# untitled.net
KiCad netlist of a schematic drawn in EAGLE
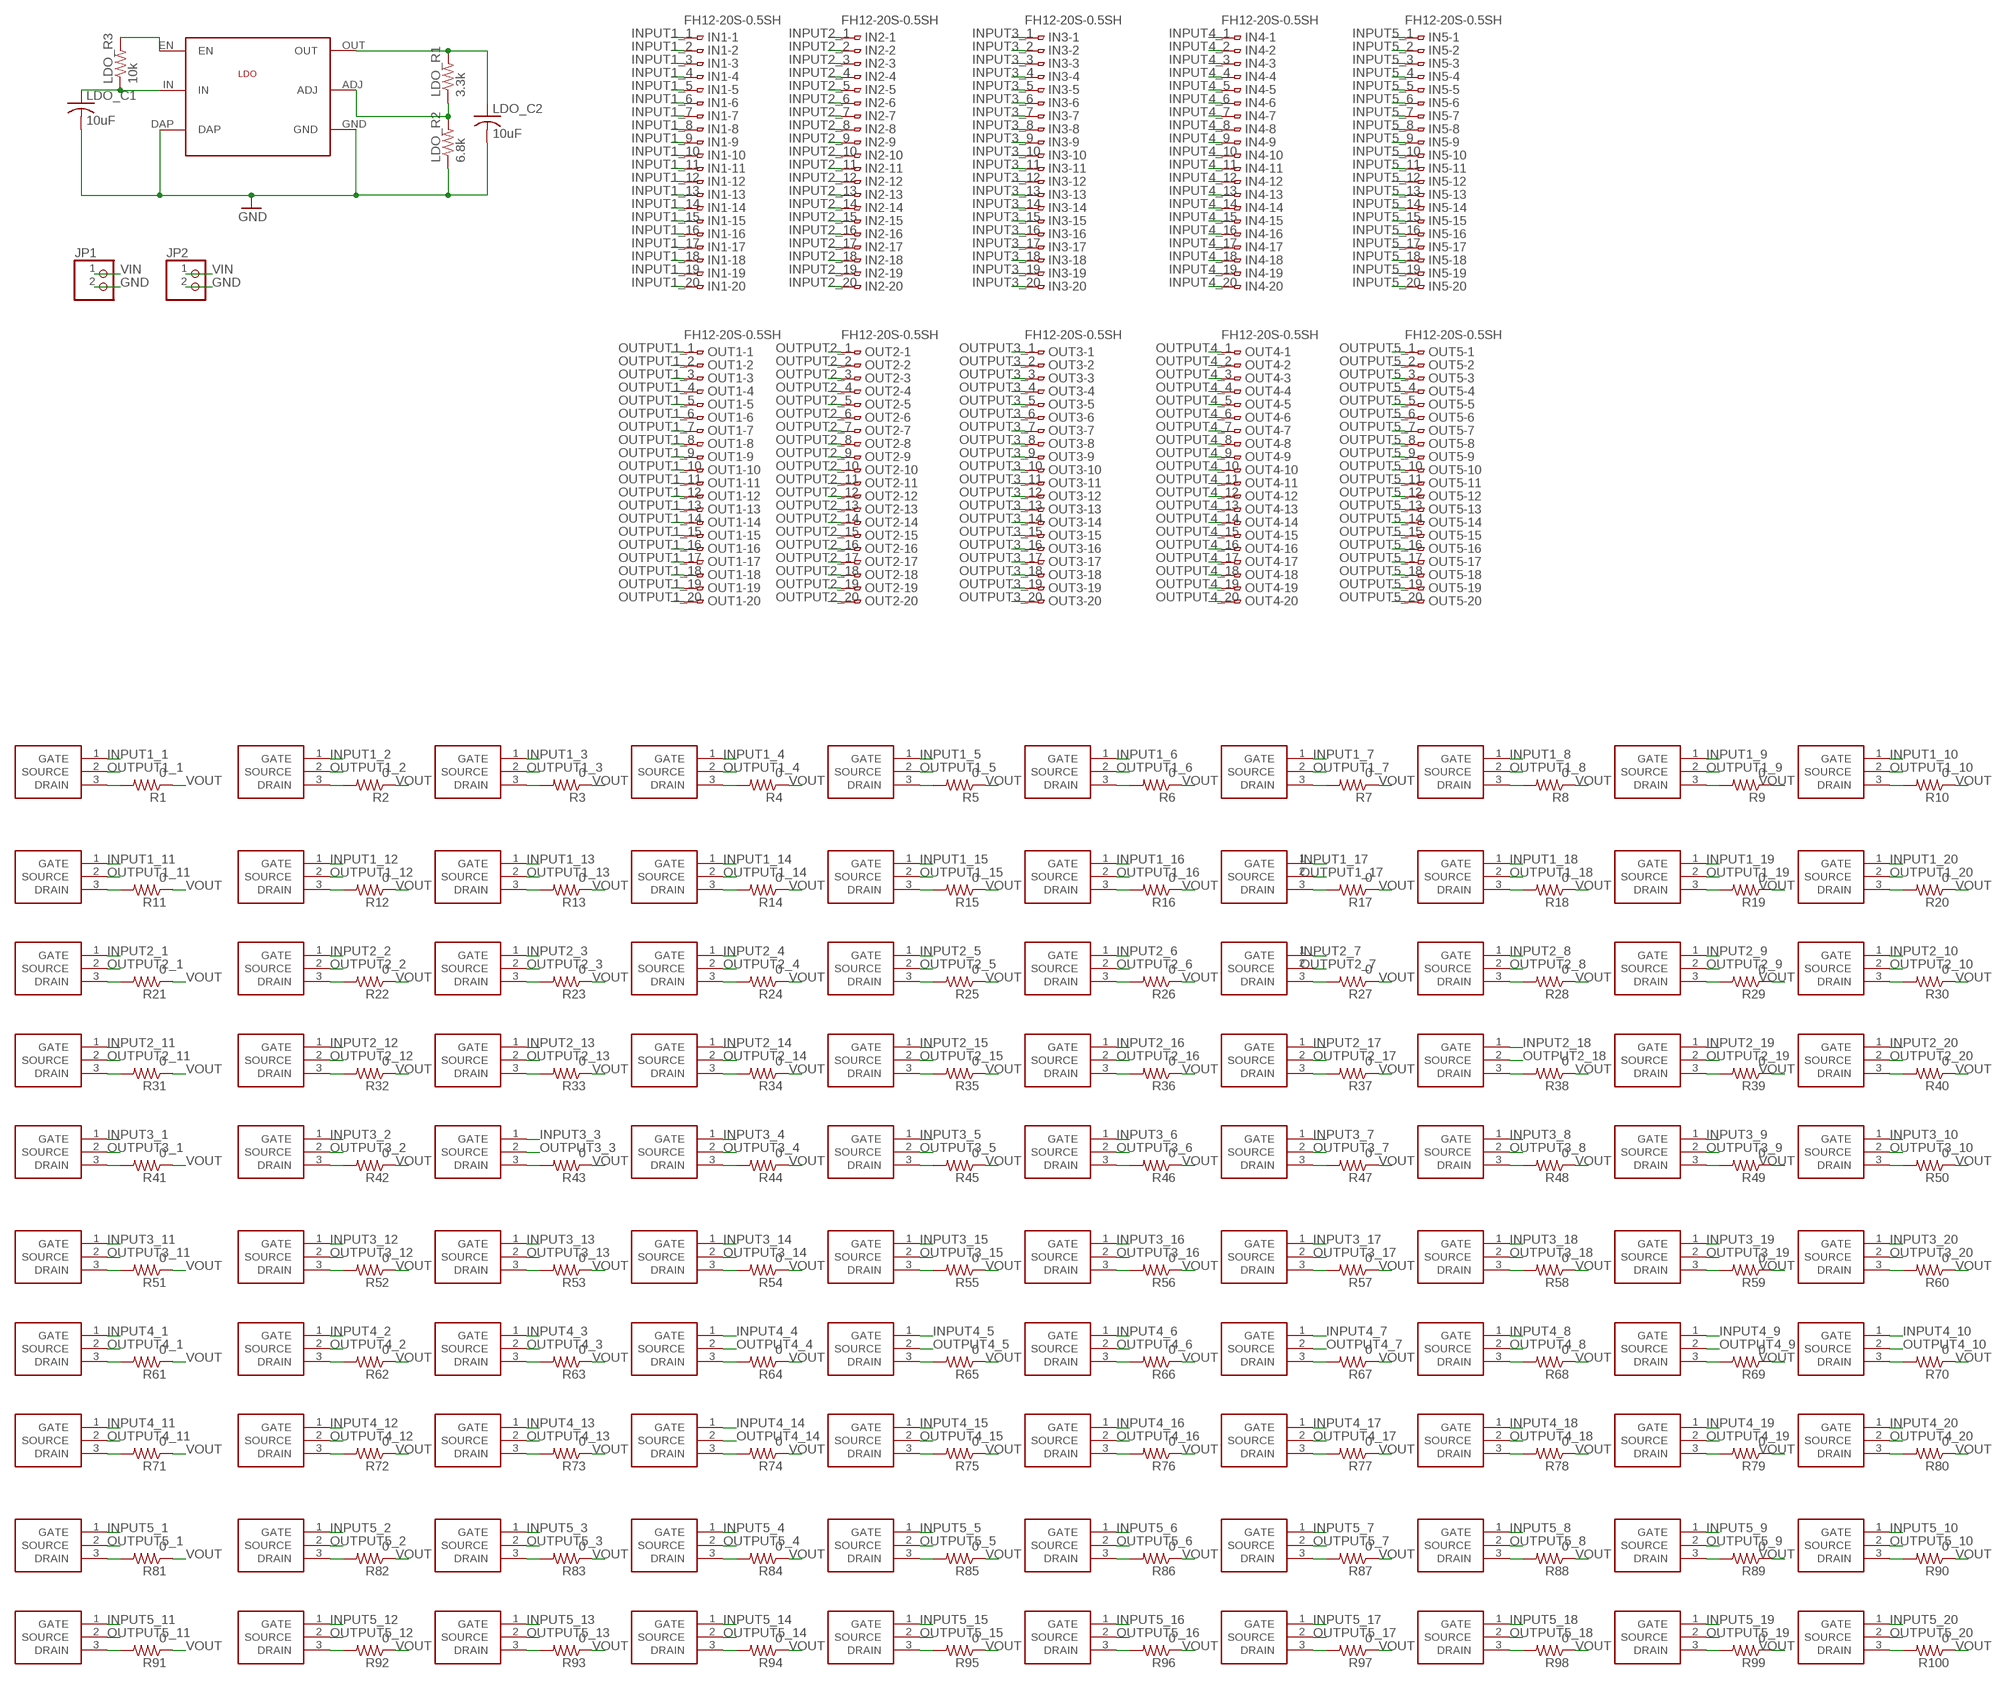
[diagram p0: schematic, sheet 1]

(export (version "E")
  (design (tool "Eeschema 10.0.6"))
  (components
    (comp (ref "IN1")
      (value "FH12-20S-0.5SH")
      (footprint "eagle-import:FH12-20S-0.5SH")
      (fields (field (name "MPN") "FH12-20S-0.5SH(55)"))
      (libsource (lib "eagle-import") (part "FH12-20S-0.5SH"))
    )
    (comp (ref "IN2")
      (value "FH12-20S-0.5SH")
      (footprint "eagle-import:FH12-20S-0.5SH")
      (fields (field (name "MPN") "FH12-20S-0.5SH(55)"))
      (libsource (lib "eagle-import") (part "FH12-20S-0.5SH"))
    )
    (comp (ref "IN3")
      (value "FH12-20S-0.5SH")
      (footprint "eagle-import:FH12-20S-0.5SH")
      (fields (field (name "MPN") "FH12-20S-0.5SH(55)"))
      (libsource (lib "eagle-import") (part "FH12-20S-0.5SH"))
    )
    (comp (ref "IN4")
      (value "FH12-20S-0.5SH")
      (footprint "eagle-import:FH12-20S-0.5SH")
      (fields (field (name "MPN") "FH12-20S-0.5SH(55)"))
      (libsource (lib "eagle-import") (part "FH12-20S-0.5SH"))
    )
    (comp (ref "IN5")
      (value "FH12-20S-0.5SH")
      (footprint "eagle-import:FH12-20S-0.5SH")
      (fields (field (name "MPN") "FH12-20S-0.5SH(55)"))
      (libsource (lib "eagle-import") (part "FH12-20S-0.5SH"))
    )
    (comp (ref "JP1")
      (value "PINHD-1X2")
      (footprint "eagle-import:1X02")
      (libsource (lib "eagle-import") (part "PINHD-1X2"))
    )
    (comp (ref "JP2")
      (value "PINHD-1X2")
      (footprint "eagle-import:1X02")
      (libsource (lib "eagle-import") (part "PINHD-1X2"))
    )
    (comp (ref "LDO")
      (value "LP38501TS_ADJ")
      (footprint "eagle-import:LP38501TS_ADJ")
      (libsource (lib "eagle-import") (part "LP38501TS_ADJ"))
    )
    (comp (ref "LDO_C1")
      (value "10uF")
      (footprint "eagle-import:C0805")
      (libsource (lib "eagle-import") (part "C-USC0805"))
    )
    (comp (ref "LDO_C2")
      (value "10uF")
      (footprint "eagle-import:C0805")
      (libsource (lib "eagle-import") (part "C-USC0805"))
    )
    (comp (ref "LDO_R1")
      (value "3.3k")
      (footprint "eagle-import:R0805")
      (libsource (lib "eagle-import") (part "R-US_R0805"))
    )
    (comp (ref "LDO_R2")
      (value "6.8k")
      (footprint "eagle-import:R0805")
      (libsource (lib "eagle-import") (part "R-US_R0805"))
    )
    (comp (ref "LDO_R3")
      (value "10k")
      (footprint "eagle-import:R0805")
      (libsource (lib "eagle-import") (part "R-US_R0805"))
    )
    (comp (ref "MOS1")
      (value "NX6008NBKNX6008NBK")
      (footprint "eagle-import:SOT95P240X110-3N")
      (libsource (lib "eagle-import") (part "NX6008NBKNX6008NBK"))
    )
    (comp (ref "MOS2")
      (value "NX6008NBKNX6008NBK")
      (footprint "eagle-import:SOT95P240X110-3N")
      (libsource (lib "eagle-import") (part "NX6008NBKNX6008NBK"))
    )
    (comp (ref "MOS3")
      (value "NX6008NBKNX6008NBK")
      (footprint "eagle-import:SOT95P240X110-3N")
      (libsource (lib "eagle-import") (part "NX6008NBKNX6008NBK"))
    )
    (comp (ref "MOS4")
      (value "NX6008NBKNX6008NBK")
      (footprint "eagle-import:SOT95P240X110-3N")
      (libsource (lib "eagle-import") (part "NX6008NBKNX6008NBK"))
    )
    (comp (ref "MOS5")
      (value "NX6008NBKNX6008NBK")
      (footprint "eagle-import:SOT95P240X110-3N")
      (libsource (lib "eagle-import") (part "NX6008NBKNX6008NBK"))
    )
    (comp (ref "MOS6")
      (value "NX6008NBKNX6008NBK")
      (footprint "eagle-import:SOT95P240X110-3N")
      (libsource (lib "eagle-import") (part "NX6008NBKNX6008NBK"))
    )
    (comp (ref "MOS7")
      (value "NX6008NBKNX6008NBK")
      (footprint "eagle-import:SOT95P240X110-3N")
      (libsource (lib "eagle-import") (part "NX6008NBKNX6008NBK"))
    )
    (comp (ref "MOS8")
      (value "NX6008NBKNX6008NBK")
      (footprint "eagle-import:SOT95P240X110-3N")
      (libsource (lib "eagle-import") (part "NX6008NBKNX6008NBK"))
    )
    (comp (ref "MOS9")
      (value "NX6008NBKNX6008NBK")
      (footprint "eagle-import:SOT95P240X110-3N")
      (libsource (lib "eagle-import") (part "NX6008NBKNX6008NBK"))
    )
    (comp (ref "MOS10")
      (value "NX6008NBKNX6008NBK")
      (footprint "eagle-import:SOT95P240X110-3N")
      (libsource (lib "eagle-import") (part "NX6008NBKNX6008NBK"))
    )
    (comp (ref "MOS11")
      (value "NX6008NBKNX6008NBK")
      (footprint "eagle-import:SOT95P240X110-3N")
      (libsource (lib "eagle-import") (part "NX6008NBKNX6008NBK"))
    )
    (comp (ref "MOS12")
      (value "NX6008NBKNX6008NBK")
      (footprint "eagle-import:SOT95P240X110-3N")
      (libsource (lib "eagle-import") (part "NX6008NBKNX6008NBK"))
    )
    (comp (ref "MOS13")
      (value "NX6008NBKNX6008NBK")
      (footprint "eagle-import:SOT95P240X110-3N")
      (libsource (lib "eagle-import") (part "NX6008NBKNX6008NBK"))
    )
    (comp (ref "MOS14")
      (value "NX6008NBKNX6008NBK")
      (footprint "eagle-import:SOT95P240X110-3N")
      (libsource (lib "eagle-import") (part "NX6008NBKNX6008NBK"))
    )
    (comp (ref "MOS15")
      (value "NX6008NBKNX6008NBK")
      (footprint "eagle-import:SOT95P240X110-3N")
      (libsource (lib "eagle-import") (part "NX6008NBKNX6008NBK"))
    )
    (comp (ref "MOS16")
      (value "NX6008NBKNX6008NBK")
      (footprint "eagle-import:SOT95P240X110-3N")
      (libsource (lib "eagle-import") (part "NX6008NBKNX6008NBK"))
    )
    (comp (ref "MOS17")
      (value "NX6008NBKNX6008NBK")
      (footprint "eagle-import:SOT95P240X110-3N")
      (libsource (lib "eagle-import") (part "NX6008NBKNX6008NBK"))
    )
    (comp (ref "MOS18")
      (value "NX6008NBKNX6008NBK")
      (footprint "eagle-import:SOT95P240X110-3N")
      (libsource (lib "eagle-import") (part "NX6008NBKNX6008NBK"))
    )
    (comp (ref "MOS19")
      (value "NX6008NBKNX6008NBK")
      (footprint "eagle-import:SOT95P240X110-3N")
      (libsource (lib "eagle-import") (part "NX6008NBKNX6008NBK"))
    )
    (comp (ref "MOS20")
      (value "NX6008NBKNX6008NBK")
      (footprint "eagle-import:SOT95P240X110-3N")
      (libsource (lib "eagle-import") (part "NX6008NBKNX6008NBK"))
    )
    (comp (ref "MOS21")
      (value "NX6008NBKNX6008NBK")
      (footprint "eagle-import:SOT95P240X110-3N")
      (libsource (lib "eagle-import") (part "NX6008NBKNX6008NBK"))
    )
    (comp (ref "MOS22")
      (value "NX6008NBKNX6008NBK")
      (footprint "eagle-import:SOT95P240X110-3N")
      (libsource (lib "eagle-import") (part "NX6008NBKNX6008NBK"))
    )
    (comp (ref "MOS23")
      (value "NX6008NBKNX6008NBK")
      (footprint "eagle-import:SOT95P240X110-3N")
      (libsource (lib "eagle-import") (part "NX6008NBKNX6008NBK"))
    )
    (comp (ref "MOS24")
      (value "NX6008NBKNX6008NBK")
      (footprint "eagle-import:SOT95P240X110-3N")
      (libsource (lib "eagle-import") (part "NX6008NBKNX6008NBK"))
    )
    (comp (ref "MOS25")
      (value "NX6008NBKNX6008NBK")
      (footprint "eagle-import:SOT95P240X110-3N")
      (libsource (lib "eagle-import") (part "NX6008NBKNX6008NBK"))
    )
    (comp (ref "MOS26")
      (value "NX6008NBKNX6008NBK")
      (footprint "eagle-import:SOT95P240X110-3N")
      (libsource (lib "eagle-import") (part "NX6008NBKNX6008NBK"))
    )
    (comp (ref "MOS27")
      (value "NX6008NBKNX6008NBK")
      (footprint "eagle-import:SOT95P240X110-3N")
      (libsource (lib "eagle-import") (part "NX6008NBKNX6008NBK"))
    )
    (comp (ref "MOS28")
      (value "NX6008NBKNX6008NBK")
      (footprint "eagle-import:SOT95P240X110-3N")
      (libsource (lib "eagle-import") (part "NX6008NBKNX6008NBK"))
    )
    (comp (ref "MOS29")
      (value "NX6008NBKNX6008NBK")
      (footprint "eagle-import:SOT95P240X110-3N")
      (libsource (lib "eagle-import") (part "NX6008NBKNX6008NBK"))
    )
    (comp (ref "MOS30")
      (value "NX6008NBKNX6008NBK")
      (footprint "eagle-import:SOT95P240X110-3N")
      (libsource (lib "eagle-import") (part "NX6008NBKNX6008NBK"))
    )
    (comp (ref "MOS31")
      (value "NX6008NBKNX6008NBK")
      (footprint "eagle-import:SOT95P240X110-3N")
      (libsource (lib "eagle-import") (part "NX6008NBKNX6008NBK"))
    )
    (comp (ref "MOS32")
      (value "NX6008NBKNX6008NBK")
      (footprint "eagle-import:SOT95P240X110-3N")
      (libsource (lib "eagle-import") (part "NX6008NBKNX6008NBK"))
    )
    (comp (ref "MOS33")
      (value "NX6008NBKNX6008NBK")
      (footprint "eagle-import:SOT95P240X110-3N")
      (libsource (lib "eagle-import") (part "NX6008NBKNX6008NBK"))
    )
    (comp (ref "MOS34")
      (value "NX6008NBKNX6008NBK")
      (footprint "eagle-import:SOT95P240X110-3N")
      (libsource (lib "eagle-import") (part "NX6008NBKNX6008NBK"))
    )
    (comp (ref "MOS35")
      (value "NX6008NBKNX6008NBK")
      (footprint "eagle-import:SOT95P240X110-3N")
      (libsource (lib "eagle-import") (part "NX6008NBKNX6008NBK"))
    )
    (comp (ref "MOS36")
      (value "NX6008NBKNX6008NBK")
      (footprint "eagle-import:SOT95P240X110-3N")
      (libsource (lib "eagle-import") (part "NX6008NBKNX6008NBK"))
    )
    (comp (ref "MOS37")
      (value "NX6008NBKNX6008NBK")
      (footprint "eagle-import:SOT95P240X110-3N")
      (libsource (lib "eagle-import") (part "NX6008NBKNX6008NBK"))
    )
    (comp (ref "MOS38")
      (value "NX6008NBKNX6008NBK")
      (footprint "eagle-import:SOT95P240X110-3N")
      (libsource (lib "eagle-import") (part "NX6008NBKNX6008NBK"))
    )
    (comp (ref "MOS39")
      (value "NX6008NBKNX6008NBK")
      (footprint "eagle-import:SOT95P240X110-3N")
      (libsource (lib "eagle-import") (part "NX6008NBKNX6008NBK"))
    )
    (comp (ref "MOS40")
      (value "NX6008NBKNX6008NBK")
      (footprint "eagle-import:SOT95P240X110-3N")
      (libsource (lib "eagle-import") (part "NX6008NBKNX6008NBK"))
    )
    (comp (ref "MOS41")
      (value "NX6008NBKNX6008NBK")
      (footprint "eagle-import:SOT95P240X110-3N")
      (libsource (lib "eagle-import") (part "NX6008NBKNX6008NBK"))
    )
    (comp (ref "MOS42")
      (value "NX6008NBKNX6008NBK")
      (footprint "eagle-import:SOT95P240X110-3N")
      (libsource (lib "eagle-import") (part "NX6008NBKNX6008NBK"))
    )
    (comp (ref "MOS43")
      (value "NX6008NBKNX6008NBK")
      (footprint "eagle-import:SOT95P240X110-3N")
      (libsource (lib "eagle-import") (part "NX6008NBKNX6008NBK"))
    )
    (comp (ref "MOS44")
      (value "NX6008NBKNX6008NBK")
      (footprint "eagle-import:SOT95P240X110-3N")
      (libsource (lib "eagle-import") (part "NX6008NBKNX6008NBK"))
    )
    (comp (ref "MOS45")
      (value "NX6008NBKNX6008NBK")
      (footprint "eagle-import:SOT95P240X110-3N")
      (libsource (lib "eagle-import") (part "NX6008NBKNX6008NBK"))
    )
    (comp (ref "MOS46")
      (value "NX6008NBKNX6008NBK")
      (footprint "eagle-import:SOT95P240X110-3N")
      (libsource (lib "eagle-import") (part "NX6008NBKNX6008NBK"))
    )
    (comp (ref "MOS47")
      (value "NX6008NBKNX6008NBK")
      (footprint "eagle-import:SOT95P240X110-3N")
      (libsource (lib "eagle-import") (part "NX6008NBKNX6008NBK"))
    )
    (comp (ref "MOS48")
      (value "NX6008NBKNX6008NBK")
      (footprint "eagle-import:SOT95P240X110-3N")
      (libsource (lib "eagle-import") (part "NX6008NBKNX6008NBK"))
    )
    (comp (ref "MOS49")
      (value "NX6008NBKNX6008NBK")
      (footprint "eagle-import:SOT95P240X110-3N")
      (libsource (lib "eagle-import") (part "NX6008NBKNX6008NBK"))
    )
    (comp (ref "MOS50")
      (value "NX6008NBKNX6008NBK")
      (footprint "eagle-import:SOT95P240X110-3N")
      (libsource (lib "eagle-import") (part "NX6008NBKNX6008NBK"))
    )
    (comp (ref "MOS51")
      (value "NX6008NBKNX6008NBK")
      (footprint "eagle-import:SOT95P240X110-3N")
      (libsource (lib "eagle-import") (part "NX6008NBKNX6008NBK"))
    )
    (comp (ref "MOS52")
      (value "NX6008NBKNX6008NBK")
      (footprint "eagle-import:SOT95P240X110-3N")
      (libsource (lib "eagle-import") (part "NX6008NBKNX6008NBK"))
    )
    (comp (ref "MOS53")
      (value "NX6008NBKNX6008NBK")
      (footprint "eagle-import:SOT95P240X110-3N")
      (libsource (lib "eagle-import") (part "NX6008NBKNX6008NBK"))
    )
    (comp (ref "MOS54")
      (value "NX6008NBKNX6008NBK")
      (footprint "eagle-import:SOT95P240X110-3N")
      (libsource (lib "eagle-import") (part "NX6008NBKNX6008NBK"))
    )
    (comp (ref "MOS55")
      (value "NX6008NBKNX6008NBK")
      (footprint "eagle-import:SOT95P240X110-3N")
      (libsource (lib "eagle-import") (part "NX6008NBKNX6008NBK"))
    )
    (comp (ref "MOS56")
      (value "NX6008NBKNX6008NBK")
      (footprint "eagle-import:SOT95P240X110-3N")
      (libsource (lib "eagle-import") (part "NX6008NBKNX6008NBK"))
    )
    (comp (ref "MOS57")
      (value "NX6008NBKNX6008NBK")
      (footprint "eagle-import:SOT95P240X110-3N")
      (libsource (lib "eagle-import") (part "NX6008NBKNX6008NBK"))
    )
    (comp (ref "MOS58")
      (value "NX6008NBKNX6008NBK")
      (footprint "eagle-import:SOT95P240X110-3N")
      (libsource (lib "eagle-import") (part "NX6008NBKNX6008NBK"))
    )
    (comp (ref "MOS59")
      (value "NX6008NBKNX6008NBK")
      (footprint "eagle-import:SOT95P240X110-3N")
      (libsource (lib "eagle-import") (part "NX6008NBKNX6008NBK"))
    )
    (comp (ref "MOS60")
      (value "NX6008NBKNX6008NBK")
      (footprint "eagle-import:SOT95P240X110-3N")
      (libsource (lib "eagle-import") (part "NX6008NBKNX6008NBK"))
    )
    (comp (ref "MOS61")
      (value "NX6008NBKNX6008NBK")
      (footprint "eagle-import:SOT95P240X110-3N")
      (libsource (lib "eagle-import") (part "NX6008NBKNX6008NBK"))
    )
    (comp (ref "MOS62")
      (value "NX6008NBKNX6008NBK")
      (footprint "eagle-import:SOT95P240X110-3N")
      (libsource (lib "eagle-import") (part "NX6008NBKNX6008NBK"))
    )
    (comp (ref "MOS63")
      (value "NX6008NBKNX6008NBK")
      (footprint "eagle-import:SOT95P240X110-3N")
      (libsource (lib "eagle-import") (part "NX6008NBKNX6008NBK"))
    )
    (comp (ref "MOS64")
      (value "NX6008NBKNX6008NBK")
      (footprint "eagle-import:SOT95P240X110-3N")
      (libsource (lib "eagle-import") (part "NX6008NBKNX6008NBK"))
    )
    (comp (ref "MOS65")
      (value "NX6008NBKNX6008NBK")
      (footprint "eagle-import:SOT95P240X110-3N")
      (libsource (lib "eagle-import") (part "NX6008NBKNX6008NBK"))
    )
    (comp (ref "MOS66")
      (value "NX6008NBKNX6008NBK")
      (footprint "eagle-import:SOT95P240X110-3N")
      (libsource (lib "eagle-import") (part "NX6008NBKNX6008NBK"))
    )
    (comp (ref "MOS67")
      (value "NX6008NBKNX6008NBK")
      (footprint "eagle-import:SOT95P240X110-3N")
      (libsource (lib "eagle-import") (part "NX6008NBKNX6008NBK"))
    )
    (comp (ref "MOS68")
      (value "NX6008NBKNX6008NBK")
      (footprint "eagle-import:SOT95P240X110-3N")
      (libsource (lib "eagle-import") (part "NX6008NBKNX6008NBK"))
    )
    (comp (ref "MOS69")
      (value "NX6008NBKNX6008NBK")
      (footprint "eagle-import:SOT95P240X110-3N")
      (libsource (lib "eagle-import") (part "NX6008NBKNX6008NBK"))
    )
    (comp (ref "MOS70")
      (value "NX6008NBKNX6008NBK")
      (footprint "eagle-import:SOT95P240X110-3N")
      (libsource (lib "eagle-import") (part "NX6008NBKNX6008NBK"))
    )
    (comp (ref "MOS71")
      (value "NX6008NBKNX6008NBK")
      (footprint "eagle-import:SOT95P240X110-3N")
      (libsource (lib "eagle-import") (part "NX6008NBKNX6008NBK"))
    )
    (comp (ref "MOS72")
      (value "NX6008NBKNX6008NBK")
      (footprint "eagle-import:SOT95P240X110-3N")
      (libsource (lib "eagle-import") (part "NX6008NBKNX6008NBK"))
    )
    (comp (ref "MOS73")
      (value "NX6008NBKNX6008NBK")
      (footprint "eagle-import:SOT95P240X110-3N")
      (libsource (lib "eagle-import") (part "NX6008NBKNX6008NBK"))
    )
    (comp (ref "MOS74")
      (value "NX6008NBKNX6008NBK")
      (footprint "eagle-import:SOT95P240X110-3N")
      (libsource (lib "eagle-import") (part "NX6008NBKNX6008NBK"))
    )
    (comp (ref "MOS75")
      (value "NX6008NBKNX6008NBK")
      (footprint "eagle-import:SOT95P240X110-3N")
      (libsource (lib "eagle-import") (part "NX6008NBKNX6008NBK"))
    )
    (comp (ref "MOS76")
      (value "NX6008NBKNX6008NBK")
      (footprint "eagle-import:SOT95P240X110-3N")
      (libsource (lib "eagle-import") (part "NX6008NBKNX6008NBK"))
    )
    (comp (ref "MOS77")
      (value "NX6008NBKNX6008NBK")
      (footprint "eagle-import:SOT95P240X110-3N")
      (libsource (lib "eagle-import") (part "NX6008NBKNX6008NBK"))
    )
    (comp (ref "MOS78")
      (value "NX6008NBKNX6008NBK")
      (footprint "eagle-import:SOT95P240X110-3N")
      (libsource (lib "eagle-import") (part "NX6008NBKNX6008NBK"))
    )
    (comp (ref "MOS79")
      (value "NX6008NBKNX6008NBK")
      (footprint "eagle-import:SOT95P240X110-3N")
      (libsource (lib "eagle-import") (part "NX6008NBKNX6008NBK"))
    )
    (comp (ref "MOS80")
      (value "NX6008NBKNX6008NBK")
      (footprint "eagle-import:SOT95P240X110-3N")
      (libsource (lib "eagle-import") (part "NX6008NBKNX6008NBK"))
    )
    (comp (ref "MOS81")
      (value "NX6008NBKNX6008NBK")
      (footprint "eagle-import:SOT95P240X110-3N")
      (libsource (lib "eagle-import") (part "NX6008NBKNX6008NBK"))
    )
    (comp (ref "MOS82")
      (value "NX6008NBKNX6008NBK")
      (footprint "eagle-import:SOT95P240X110-3N")
      (libsource (lib "eagle-import") (part "NX6008NBKNX6008NBK"))
    )
    (comp (ref "MOS83")
      (value "NX6008NBKNX6008NBK")
      (footprint "eagle-import:SOT95P240X110-3N")
      (libsource (lib "eagle-import") (part "NX6008NBKNX6008NBK"))
    )
    (comp (ref "MOS84")
      (value "NX6008NBKNX6008NBK")
      (footprint "eagle-import:SOT95P240X110-3N")
      (libsource (lib "eagle-import") (part "NX6008NBKNX6008NBK"))
    )
    (comp (ref "MOS85")
      (value "NX6008NBKNX6008NBK")
      (footprint "eagle-import:SOT95P240X110-3N")
      (libsource (lib "eagle-import") (part "NX6008NBKNX6008NBK"))
    )
    (comp (ref "MOS86")
      (value "NX6008NBKNX6008NBK")
      (footprint "eagle-import:SOT95P240X110-3N")
      (libsource (lib "eagle-import") (part "NX6008NBKNX6008NBK"))
    )
    (comp (ref "MOS87")
      (value "NX6008NBKNX6008NBK")
      (footprint "eagle-import:SOT95P240X110-3N")
      (libsource (lib "eagle-import") (part "NX6008NBKNX6008NBK"))
    )
    (comp (ref "MOS88")
      (value "NX6008NBKNX6008NBK")
      (footprint "eagle-import:SOT95P240X110-3N")
      (libsource (lib "eagle-import") (part "NX6008NBKNX6008NBK"))
    )
    (comp (ref "MOS89")
      (value "NX6008NBKNX6008NBK")
      (footprint "eagle-import:SOT95P240X110-3N")
      (libsource (lib "eagle-import") (part "NX6008NBKNX6008NBK"))
    )
    (comp (ref "MOS90")
      (value "NX6008NBKNX6008NBK")
      (footprint "eagle-import:SOT95P240X110-3N")
      (libsource (lib "eagle-import") (part "NX6008NBKNX6008NBK"))
    )
    (comp (ref "MOS91")
      (value "NX6008NBKNX6008NBK")
      (footprint "eagle-import:SOT95P240X110-3N")
      (libsource (lib "eagle-import") (part "NX6008NBKNX6008NBK"))
    )
    (comp (ref "MOS92")
      (value "NX6008NBKNX6008NBK")
      (footprint "eagle-import:SOT95P240X110-3N")
      (libsource (lib "eagle-import") (part "NX6008NBKNX6008NBK"))
    )
    (comp (ref "MOS93")
      (value "NX6008NBKNX6008NBK")
      (footprint "eagle-import:SOT95P240X110-3N")
      (libsource (lib "eagle-import") (part "NX6008NBKNX6008NBK"))
    )
    (comp (ref "MOS94")
      (value "NX6008NBKNX6008NBK")
      (footprint "eagle-import:SOT95P240X110-3N")
      (libsource (lib "eagle-import") (part "NX6008NBKNX6008NBK"))
    )
    (comp (ref "MOS95")
      (value "NX6008NBKNX6008NBK")
      (footprint "eagle-import:SOT95P240X110-3N")
      (libsource (lib "eagle-import") (part "NX6008NBKNX6008NBK"))
    )
    (comp (ref "MOS96")
      (value "NX6008NBKNX6008NBK")
      (footprint "eagle-import:SOT95P240X110-3N")
      (libsource (lib "eagle-import") (part "NX6008NBKNX6008NBK"))
    )
    (comp (ref "MOS97")
      (value "NX6008NBKNX6008NBK")
      (footprint "eagle-import:SOT95P240X110-3N")
      (libsource (lib "eagle-import") (part "NX6008NBKNX6008NBK"))
    )
    (comp (ref "MOS98")
      (value "NX6008NBKNX6008NBK")
      (footprint "eagle-import:SOT95P240X110-3N")
      (libsource (lib "eagle-import") (part "NX6008NBKNX6008NBK"))
    )
    (comp (ref "MOS99")
      (value "NX6008NBKNX6008NBK")
      (footprint "eagle-import:SOT95P240X110-3N")
      (libsource (lib "eagle-import") (part "NX6008NBKNX6008NBK"))
    )
    (comp (ref "MOS100")
      (value "NX6008NBKNX6008NBK")
      (footprint "eagle-import:SOT95P240X110-3N")
      (libsource (lib "eagle-import") (part "NX6008NBKNX6008NBK"))
    )
    (comp (ref "OUT1")
      (value "FH12-20S-0.5SH")
      (footprint "eagle-import:FH12-20S-0.5SH")
      (fields (field (name "MPN") "FH12-20S-0.5SH(55)"))
      (libsource (lib "eagle-import") (part "FH12-20S-0.5SH"))
    )
    (comp (ref "OUT2")
      (value "FH12-20S-0.5SH")
      (footprint "eagle-import:FH12-20S-0.5SH")
      (fields (field (name "MPN") "FH12-20S-0.5SH(55)"))
      (libsource (lib "eagle-import") (part "FH12-20S-0.5SH"))
    )
    (comp (ref "OUT3")
      (value "FH12-20S-0.5SH")
      (footprint "eagle-import:FH12-20S-0.5SH")
      (fields (field (name "MPN") "FH12-20S-0.5SH(55)"))
      (libsource (lib "eagle-import") (part "FH12-20S-0.5SH"))
    )
    (comp (ref "OUT4")
      (value "FH12-20S-0.5SH")
      (footprint "eagle-import:FH12-20S-0.5SH")
      (fields (field (name "MPN") "FH12-20S-0.5SH(55)"))
      (libsource (lib "eagle-import") (part "FH12-20S-0.5SH"))
    )
    (comp (ref "OUT5")
      (value "FH12-20S-0.5SH")
      (footprint "eagle-import:FH12-20S-0.5SH")
      (fields (field (name "MPN") "FH12-20S-0.5SH(55)"))
      (libsource (lib "eagle-import") (part "FH12-20S-0.5SH"))
    )
    (comp (ref "R1")
      (value "0")
      (footprint "eagle-import:R0805")
      (libsource (lib "eagle-import") (part "R-US_R0805"))
    )
    (comp (ref "R2")
      (value "0")
      (footprint "eagle-import:R0805")
      (libsource (lib "eagle-import") (part "R-US_R0805"))
    )
    (comp (ref "R3")
      (value "0")
      (footprint "eagle-import:R0805")
      (libsource (lib "eagle-import") (part "R-US_R0805"))
    )
    (comp (ref "R4")
      (value "0")
      (footprint "eagle-import:R0805")
      (libsource (lib "eagle-import") (part "R-US_R0805"))
    )
    (comp (ref "R5")
      (value "0")
      (footprint "eagle-import:R0805")
      (libsource (lib "eagle-import") (part "R-US_R0805"))
    )
    (comp (ref "R6")
      (value "0")
      (footprint "eagle-import:R0805")
      (libsource (lib "eagle-import") (part "R-US_R0805"))
    )
    (comp (ref "R7")
      (value "0")
      (footprint "eagle-import:R0805")
      (libsource (lib "eagle-import") (part "R-US_R0805"))
    )
    (comp (ref "R8")
      (value "0")
      (footprint "eagle-import:R0805")
      (libsource (lib "eagle-import") (part "R-US_R0805"))
    )
    (comp (ref "R9")
      (value "0")
      (footprint "eagle-import:R0805")
      (libsource (lib "eagle-import") (part "R-US_R0805"))
    )
    (comp (ref "R10")
      (value "0")
      (footprint "eagle-import:R0805")
      (libsource (lib "eagle-import") (part "R-US_R0805"))
    )
    (comp (ref "R11")
      (value "0")
      (footprint "eagle-import:R0805")
      (libsource (lib "eagle-import") (part "R-US_R0805"))
    )
    (comp (ref "R12")
      (value "0")
      (footprint "eagle-import:R0805")
      (libsource (lib "eagle-import") (part "R-US_R0805"))
    )
    (comp (ref "R13")
      (value "0")
      (footprint "eagle-import:R0805")
      (libsource (lib "eagle-import") (part "R-US_R0805"))
    )
    (comp (ref "R14")
      (value "0")
      (footprint "eagle-import:R0805")
      (libsource (lib "eagle-import") (part "R-US_R0805"))
    )
    (comp (ref "R15")
      (value "0")
      (footprint "eagle-import:R0805")
      (libsource (lib "eagle-import") (part "R-US_R0805"))
    )
    (comp (ref "R16")
      (value "0")
      (footprint "eagle-import:R0805")
      (libsource (lib "eagle-import") (part "R-US_R0805"))
    )
    (comp (ref "R17")
      (value "0")
      (footprint "eagle-import:R0805")
      (libsource (lib "eagle-import") (part "R-US_R0805"))
    )
    (comp (ref "R18")
      (value "0")
      (footprint "eagle-import:R0805")
      (libsource (lib "eagle-import") (part "R-US_R0805"))
    )
    (comp (ref "R19")
      (value "0")
      (footprint "eagle-import:R0805")
      (libsource (lib "eagle-import") (part "R-US_R0805"))
    )
    (comp (ref "R20")
      (value "0")
      (footprint "eagle-import:R0805")
      (libsource (lib "eagle-import") (part "R-US_R0805"))
    )
    (comp (ref "R21")
      (value "0")
      (footprint "eagle-import:R0805")
      (libsource (lib "eagle-import") (part "R-US_R0805"))
    )
    (comp (ref "R22")
      (value "0")
      (footprint "eagle-import:R0805")
      (libsource (lib "eagle-import") (part "R-US_R0805"))
    )
    (comp (ref "R23")
      (value "0")
      (footprint "eagle-import:R0805")
      (libsource (lib "eagle-import") (part "R-US_R0805"))
    )
    (comp (ref "R24")
      (value "0")
      (footprint "eagle-import:R0805")
      (libsource (lib "eagle-import") (part "R-US_R0805"))
    )
    (comp (ref "R25")
      (value "0")
      (footprint "eagle-import:R0805")
      (libsource (lib "eagle-import") (part "R-US_R0805"))
    )
    (comp (ref "R26")
      (value "0")
      (footprint "eagle-import:R0805")
      (libsource (lib "eagle-import") (part "R-US_R0805"))
    )
    (comp (ref "R27")
      (value "0")
      (footprint "eagle-import:R0805")
      (libsource (lib "eagle-import") (part "R-US_R0805"))
    )
    (comp (ref "R28")
      (value "0")
      (footprint "eagle-import:R0805")
      (libsource (lib "eagle-import") (part "R-US_R0805"))
    )
    (comp (ref "R29")
      (value "0")
      (footprint "eagle-import:R0805")
      (libsource (lib "eagle-import") (part "R-US_R0805"))
    )
    (comp (ref "R30")
      (value "0")
      (footprint "eagle-import:R0805")
      (libsource (lib "eagle-import") (part "R-US_R0805"))
    )
    (comp (ref "R31")
      (value "0")
      (footprint "eagle-import:R0805")
      (libsource (lib "eagle-import") (part "R-US_R0805"))
    )
    (comp (ref "R32")
      (value "0")
      (footprint "eagle-import:R0805")
      (libsource (lib "eagle-import") (part "R-US_R0805"))
    )
    (comp (ref "R33")
      (value "0")
      (footprint "eagle-import:R0805")
      (libsource (lib "eagle-import") (part "R-US_R0805"))
    )
    (comp (ref "R34")
      (value "0")
      (footprint "eagle-import:R0805")
      (libsource (lib "eagle-import") (part "R-US_R0805"))
    )
    (comp (ref "R35")
      (value "0")
      (footprint "eagle-import:R0805")
      (libsource (lib "eagle-import") (part "R-US_R0805"))
    )
    (comp (ref "R36")
      (value "0")
      (footprint "eagle-import:R0805")
      (libsource (lib "eagle-import") (part "R-US_R0805"))
    )
    (comp (ref "R37")
      (value "0")
      (footprint "eagle-import:R0805")
      (libsource (lib "eagle-import") (part "R-US_R0805"))
    )
    (comp (ref "R38")
      (value "0")
      (footprint "eagle-import:R0805")
      (libsource (lib "eagle-import") (part "R-US_R0805"))
    )
    (comp (ref "R39")
      (value "0")
      (footprint "eagle-import:R0805")
      (libsource (lib "eagle-import") (part "R-US_R0805"))
    )
    (comp (ref "R40")
      (value "0")
      (footprint "eagle-import:R0805")
      (libsource (lib "eagle-import") (part "R-US_R0805"))
    )
    (comp (ref "R41")
      (value "0")
      (footprint "eagle-import:R0805")
      (libsource (lib "eagle-import") (part "R-US_R0805"))
    )
    (comp (ref "R42")
      (value "0")
      (footprint "eagle-import:R0805")
      (libsource (lib "eagle-import") (part "R-US_R0805"))
    )
    (comp (ref "R43")
      (value "0")
      (footprint "eagle-import:R0805")
      (libsource (lib "eagle-import") (part "R-US_R0805"))
    )
    (comp (ref "R44")
      (value "0")
      (footprint "eagle-import:R0805")
      (libsource (lib "eagle-import") (part "R-US_R0805"))
    )
    (comp (ref "R45")
      (value "0")
      (footprint "eagle-import:R0805")
      (libsource (lib "eagle-import") (part "R-US_R0805"))
    )
    (comp (ref "R46")
      (value "0")
      (footprint "eagle-import:R0805")
      (libsource (lib "eagle-import") (part "R-US_R0805"))
    )
    (comp (ref "R47")
      (value "0")
      (footprint "eagle-import:R0805")
      (libsource (lib "eagle-import") (part "R-US_R0805"))
    )
    (comp (ref "R48")
      (value "0")
      (footprint "eagle-import:R0805")
      (libsource (lib "eagle-import") (part "R-US_R0805"))
    )
    (comp (ref "R49")
      (value "0")
      (footprint "eagle-import:R0805")
      (libsource (lib "eagle-import") (part "R-US_R0805"))
    )
    (comp (ref "R50")
      (value "0")
      (footprint "eagle-import:R0805")
      (libsource (lib "eagle-import") (part "R-US_R0805"))
    )
    (comp (ref "R51")
      (value "0")
      (footprint "eagle-import:R0805")
      (libsource (lib "eagle-import") (part "R-US_R0805"))
    )
    (comp (ref "R52")
      (value "0")
      (footprint "eagle-import:R0805")
      (libsource (lib "eagle-import") (part "R-US_R0805"))
    )
    (comp (ref "R53")
      (value "0")
      (footprint "eagle-import:R0805")
      (libsource (lib "eagle-import") (part "R-US_R0805"))
    )
    (comp (ref "R54")
      (value "0")
      (footprint "eagle-import:R0805")
      (libsource (lib "eagle-import") (part "R-US_R0805"))
    )
    (comp (ref "R55")
      (value "0")
      (footprint "eagle-import:R0805")
      (libsource (lib "eagle-import") (part "R-US_R0805"))
    )
    (comp (ref "R56")
      (value "0")
      (footprint "eagle-import:R0805")
      (libsource (lib "eagle-import") (part "R-US_R0805"))
    )
    (comp (ref "R57")
      (value "0")
      (footprint "eagle-import:R0805")
      (libsource (lib "eagle-import") (part "R-US_R0805"))
    )
    (comp (ref "R58")
      (value "0")
      (footprint "eagle-import:R0805")
      (libsource (lib "eagle-import") (part "R-US_R0805"))
    )
    (comp (ref "R59")
      (value "0")
      (footprint "eagle-import:R0805")
      (libsource (lib "eagle-import") (part "R-US_R0805"))
    )
    (comp (ref "R60")
      (value "0")
      (footprint "eagle-import:R0805")
      (libsource (lib "eagle-import") (part "R-US_R0805"))
    )
    (comp (ref "R61")
      (value "0")
      (footprint "eagle-import:R0805")
      (libsource (lib "eagle-import") (part "R-US_R0805"))
    )
    (comp (ref "R62")
      (value "0")
      (footprint "eagle-import:R0805")
      (libsource (lib "eagle-import") (part "R-US_R0805"))
    )
    (comp (ref "R63")
      (value "0")
      (footprint "eagle-import:R0805")
      (libsource (lib "eagle-import") (part "R-US_R0805"))
    )
    (comp (ref "R64")
      (value "0")
      (footprint "eagle-import:R0805")
      (libsource (lib "eagle-import") (part "R-US_R0805"))
    )
    (comp (ref "R65")
      (value "0")
      (footprint "eagle-import:R0805")
      (libsource (lib "eagle-import") (part "R-US_R0805"))
    )
    (comp (ref "R66")
      (value "0")
      (footprint "eagle-import:R0805")
      (libsource (lib "eagle-import") (part "R-US_R0805"))
    )
    (comp (ref "R67")
      (value "0")
      (footprint "eagle-import:R0805")
      (libsource (lib "eagle-import") (part "R-US_R0805"))
    )
    (comp (ref "R68")
      (value "0")
      (footprint "eagle-import:R0805")
      (libsource (lib "eagle-import") (part "R-US_R0805"))
    )
    (comp (ref "R69")
      (value "0")
      (footprint "eagle-import:R0805")
      (libsource (lib "eagle-import") (part "R-US_R0805"))
    )
    (comp (ref "R70")
      (value "0")
      (footprint "eagle-import:R0805")
      (libsource (lib "eagle-import") (part "R-US_R0805"))
    )
    (comp (ref "R71")
      (value "0")
      (footprint "eagle-import:R0805")
      (libsource (lib "eagle-import") (part "R-US_R0805"))
    )
    (comp (ref "R72")
      (value "0")
      (footprint "eagle-import:R0805")
      (libsource (lib "eagle-import") (part "R-US_R0805"))
    )
    (comp (ref "R73")
      (value "0")
      (footprint "eagle-import:R0805")
      (libsource (lib "eagle-import") (part "R-US_R0805"))
    )
    (comp (ref "R74")
      (value "0")
      (footprint "eagle-import:R0805")
      (libsource (lib "eagle-import") (part "R-US_R0805"))
    )
    (comp (ref "R75")
      (value "0")
      (footprint "eagle-import:R0805")
      (libsource (lib "eagle-import") (part "R-US_R0805"))
    )
    (comp (ref "R76")
      (value "0")
      (footprint "eagle-import:R0805")
      (libsource (lib "eagle-import") (part "R-US_R0805"))
    )
    (comp (ref "R77")
      (value "0")
      (footprint "eagle-import:R0805")
      (libsource (lib "eagle-import") (part "R-US_R0805"))
    )
    (comp (ref "R78")
      (value "0")
      (footprint "eagle-import:R0805")
      (libsource (lib "eagle-import") (part "R-US_R0805"))
    )
    (comp (ref "R79")
      (value "0")
      (footprint "eagle-import:R0805")
      (libsource (lib "eagle-import") (part "R-US_R0805"))
    )
    (comp (ref "R80")
      (value "0")
      (footprint "eagle-import:R0805")
      (libsource (lib "eagle-import") (part "R-US_R0805"))
    )
    (comp (ref "R81")
      (value "0")
      (footprint "eagle-import:R0805")
      (libsource (lib "eagle-import") (part "R-US_R0805"))
    )
    (comp (ref "R82")
      (value "0")
      (footprint "eagle-import:R0805")
      (libsource (lib "eagle-import") (part "R-US_R0805"))
    )
    (comp (ref "R83")
      (value "0")
      (footprint "eagle-import:R0805")
      (libsource (lib "eagle-import") (part "R-US_R0805"))
    )
    (comp (ref "R84")
      (value "0")
      (footprint "eagle-import:R0805")
      (libsource (lib "eagle-import") (part "R-US_R0805"))
    )
    (comp (ref "R85")
      (value "0")
      (footprint "eagle-import:R0805")
      (libsource (lib "eagle-import") (part "R-US_R0805"))
    )
    (comp (ref "R86")
      (value "0")
      (footprint "eagle-import:R0805")
      (libsource (lib "eagle-import") (part "R-US_R0805"))
    )
    (comp (ref "R87")
      (value "0")
      (footprint "eagle-import:R0805")
      (libsource (lib "eagle-import") (part "R-US_R0805"))
    )
    (comp (ref "R88")
      (value "0")
      (footprint "eagle-import:R0805")
      (libsource (lib "eagle-import") (part "R-US_R0805"))
    )
    (comp (ref "R89")
      (value "0")
      (footprint "eagle-import:R0805")
      (libsource (lib "eagle-import") (part "R-US_R0805"))
    )
    (comp (ref "R90")
      (value "0")
      (footprint "eagle-import:R0805")
      (libsource (lib "eagle-import") (part "R-US_R0805"))
    )
    (comp (ref "R91")
      (value "0")
      (footprint "eagle-import:R0805")
      (libsource (lib "eagle-import") (part "R-US_R0805"))
    )
    (comp (ref "R92")
      (value "0")
      (footprint "eagle-import:R0805")
      (libsource (lib "eagle-import") (part "R-US_R0805"))
    )
    (comp (ref "R93")
      (value "0")
      (footprint "eagle-import:R0805")
      (libsource (lib "eagle-import") (part "R-US_R0805"))
    )
    (comp (ref "R94")
      (value "0")
      (footprint "eagle-import:R0805")
      (libsource (lib "eagle-import") (part "R-US_R0805"))
    )
    (comp (ref "R95")
      (value "0")
      (footprint "eagle-import:R0805")
      (libsource (lib "eagle-import") (part "R-US_R0805"))
    )
    (comp (ref "R96")
      (value "0")
      (footprint "eagle-import:R0805")
      (libsource (lib "eagle-import") (part "R-US_R0805"))
    )
    (comp (ref "R97")
      (value "0")
      (footprint "eagle-import:R0805")
      (libsource (lib "eagle-import") (part "R-US_R0805"))
    )
    (comp (ref "R98")
      (value "0")
      (footprint "eagle-import:R0805")
      (libsource (lib "eagle-import") (part "R-US_R0805"))
    )
    (comp (ref "R99")
      (value "0")
      (footprint "eagle-import:R0805")
      (libsource (lib "eagle-import") (part "R-US_R0805"))
    )
    (comp (ref "R100")
      (value "0")
      (footprint "eagle-import:R0805")
      (libsource (lib "eagle-import") (part "R-US_R0805"))
    )
  )
  (nets
    (net (code "1") (name "/INPUT1_1") (class "Default")
      (node (ref "IN1") (pin "1") (pinfunction "1_1") (pintype "passive"))
      (node (ref "MOS1") (pin "1") (pinfunction "GATE_1") (pintype "bidirectional"))
    )
    (net (code "2") (name "/INPUT1_2") (class "Default")
      (node (ref "IN1") (pin "2") (pinfunction "1_2") (pintype "passive"))
      (node (ref "MOS2") (pin "1") (pinfunction "GATE_1") (pintype "bidirectional"))
    )
    (net (code "3") (name "/INPUT1_3") (class "Default")
      (node (ref "IN1") (pin "3") (pinfunction "1_3") (pintype "passive"))
      (node (ref "MOS3") (pin "1") (pinfunction "GATE_1") (pintype "bidirectional"))
    )
    (net (code "4") (name "/INPUT1_4") (class "Default")
      (node (ref "IN1") (pin "4") (pinfunction "1_4") (pintype "passive"))
      (node (ref "MOS4") (pin "1") (pinfunction "GATE_1") (pintype "bidirectional"))
    )
    (net (code "5") (name "/INPUT1_5") (class "Default")
      (node (ref "IN1") (pin "5") (pinfunction "1_5") (pintype "passive"))
      (node (ref "MOS5") (pin "1") (pinfunction "GATE_1") (pintype "bidirectional"))
    )
    (net (code "6") (name "/INPUT1_6") (class "Default")
      (node (ref "IN1") (pin "6") (pinfunction "1_6") (pintype "passive"))
      (node (ref "MOS6") (pin "1") (pinfunction "GATE_1") (pintype "bidirectional"))
    )
    (net (code "7") (name "/INPUT1_7") (class "Default")
      (node (ref "IN1") (pin "7") (pinfunction "1_7") (pintype "passive"))
      (node (ref "MOS7") (pin "1") (pinfunction "GATE_1") (pintype "bidirectional"))
    )
    (net (code "8") (name "/INPUT1_8") (class "Default")
      (node (ref "IN1") (pin "8") (pinfunction "1_8") (pintype "passive"))
      (node (ref "MOS8") (pin "1") (pinfunction "GATE_1") (pintype "bidirectional"))
    )
    (net (code "9") (name "/INPUT1_9") (class "Default")
      (node (ref "IN1") (pin "9") (pinfunction "1_9") (pintype "passive"))
      (node (ref "MOS9") (pin "1") (pinfunction "GATE_1") (pintype "bidirectional"))
    )
    (net (code "10") (name "/INPUT1_10") (class "Default")
      (node (ref "IN1") (pin "10") (pinfunction "1_10") (pintype "passive"))
      (node (ref "MOS10") (pin "1") (pinfunction "GATE_1") (pintype "bidirectional"))
    )
    (net (code "11") (name "/INPUT1_11") (class "Default")
      (node (ref "IN1") (pin "11") (pinfunction "1_11") (pintype "passive"))
      (node (ref "MOS11") (pin "1") (pinfunction "GATE_1") (pintype "bidirectional"))
    )
    (net (code "12") (name "/INPUT1_12") (class "Default")
      (node (ref "IN1") (pin "12") (pinfunction "1_12") (pintype "passive"))
      (node (ref "MOS12") (pin "1") (pinfunction "GATE_1") (pintype "bidirectional"))
    )
    (net (code "13") (name "/INPUT1_13") (class "Default")
      (node (ref "IN1") (pin "13") (pinfunction "1_13") (pintype "passive"))
      (node (ref "MOS13") (pin "1") (pinfunction "GATE_1") (pintype "bidirectional"))
    )
    (net (code "14") (name "/INPUT1_14") (class "Default")
      (node (ref "IN1") (pin "14") (pinfunction "1_14") (pintype "passive"))
      (node (ref "MOS14") (pin "1") (pinfunction "GATE_1") (pintype "bidirectional"))
    )
    (net (code "15") (name "/INPUT1_15") (class "Default")
      (node (ref "IN1") (pin "15") (pinfunction "1_15") (pintype "passive"))
      (node (ref "MOS15") (pin "1") (pinfunction "GATE_1") (pintype "bidirectional"))
    )
    (net (code "16") (name "/INPUT1_16") (class "Default")
      (node (ref "IN1") (pin "16") (pinfunction "1_16") (pintype "passive"))
      (node (ref "MOS16") (pin "1") (pinfunction "GATE_1") (pintype "bidirectional"))
    )
    (net (code "17") (name "/INPUT1_17") (class "Default")
      (node (ref "IN1") (pin "17") (pinfunction "1_17") (pintype "passive"))
      (node (ref "MOS17") (pin "1") (pinfunction "GATE_1") (pintype "bidirectional"))
    )
    (net (code "18") (name "/INPUT1_18") (class "Default")
      (node (ref "IN1") (pin "18") (pinfunction "1_18") (pintype "passive"))
      (node (ref "MOS18") (pin "1") (pinfunction "GATE_1") (pintype "bidirectional"))
    )
    (net (code "19") (name "/INPUT1_19") (class "Default")
      (node (ref "IN1") (pin "19") (pinfunction "1_19") (pintype "passive"))
      (node (ref "MOS19") (pin "1") (pinfunction "GATE_1") (pintype "bidirectional"))
    )
    (net (code "20") (name "/INPUT1_20") (class "Default")
      (node (ref "IN1") (pin "20") (pinfunction "1_20") (pintype "passive"))
      (node (ref "MOS20") (pin "1") (pinfunction "GATE_1") (pintype "bidirectional"))
    )
    (net (code "21") (name "/INPUT2_1") (class "Default")
      (node (ref "IN2") (pin "1") (pinfunction "1_1") (pintype "passive"))
      (node (ref "MOS21") (pin "1") (pinfunction "GATE_1") (pintype "bidirectional"))
    )
    (net (code "22") (name "/INPUT2_2") (class "Default")
      (node (ref "IN2") (pin "2") (pinfunction "1_2") (pintype "passive"))
      (node (ref "MOS22") (pin "1") (pinfunction "GATE_1") (pintype "bidirectional"))
    )
    (net (code "23") (name "/INPUT2_3") (class "Default")
      (node (ref "IN2") (pin "3") (pinfunction "1_3") (pintype "passive"))
      (node (ref "MOS23") (pin "1") (pinfunction "GATE_1") (pintype "bidirectional"))
    )
    (net (code "24") (name "/INPUT2_4") (class "Default")
      (node (ref "IN2") (pin "4") (pinfunction "1_4") (pintype "passive"))
      (node (ref "MOS24") (pin "1") (pinfunction "GATE_1") (pintype "bidirectional"))
    )
    (net (code "25") (name "/INPUT2_5") (class "Default")
      (node (ref "IN2") (pin "5") (pinfunction "1_5") (pintype "passive"))
      (node (ref "MOS25") (pin "1") (pinfunction "GATE_1") (pintype "bidirectional"))
    )
    (net (code "26") (name "/INPUT2_6") (class "Default")
      (node (ref "IN2") (pin "6") (pinfunction "1_6") (pintype "passive"))
      (node (ref "MOS26") (pin "1") (pinfunction "GATE_1") (pintype "bidirectional"))
    )
    (net (code "27") (name "/INPUT2_7") (class "Default")
      (node (ref "IN2") (pin "7") (pinfunction "1_7") (pintype "passive"))
      (node (ref "MOS27") (pin "1") (pinfunction "GATE_1") (pintype "bidirectional"))
    )
    (net (code "28") (name "/INPUT2_8") (class "Default")
      (node (ref "IN2") (pin "8") (pinfunction "1_8") (pintype "passive"))
      (node (ref "MOS28") (pin "1") (pinfunction "GATE_1") (pintype "bidirectional"))
    )
    (net (code "29") (name "/INPUT2_9") (class "Default")
      (node (ref "IN2") (pin "9") (pinfunction "1_9") (pintype "passive"))
      (node (ref "MOS29") (pin "1") (pinfunction "GATE_1") (pintype "bidirectional"))
    )
    (net (code "30") (name "/INPUT2_10") (class "Default")
      (node (ref "IN2") (pin "10") (pinfunction "1_10") (pintype "passive"))
      (node (ref "MOS30") (pin "1") (pinfunction "GATE_1") (pintype "bidirectional"))
    )
    (net (code "31") (name "/INPUT2_11") (class "Default")
      (node (ref "IN2") (pin "11") (pinfunction "1_11") (pintype "passive"))
      (node (ref "MOS31") (pin "1") (pinfunction "GATE_1") (pintype "bidirectional"))
    )
    (net (code "32") (name "/INPUT2_12") (class "Default")
      (node (ref "IN2") (pin "12") (pinfunction "1_12") (pintype "passive"))
      (node (ref "MOS32") (pin "1") (pinfunction "GATE_1") (pintype "bidirectional"))
    )
    (net (code "33") (name "/INPUT2_13") (class "Default")
      (node (ref "IN2") (pin "13") (pinfunction "1_13") (pintype "passive"))
      (node (ref "MOS33") (pin "1") (pinfunction "GATE_1") (pintype "bidirectional"))
    )
    (net (code "34") (name "/INPUT2_14") (class "Default")
      (node (ref "IN2") (pin "14") (pinfunction "1_14") (pintype "passive"))
      (node (ref "MOS34") (pin "1") (pinfunction "GATE_1") (pintype "bidirectional"))
    )
    (net (code "35") (name "/INPUT2_15") (class "Default")
      (node (ref "IN2") (pin "15") (pinfunction "1_15") (pintype "passive"))
      (node (ref "MOS35") (pin "1") (pinfunction "GATE_1") (pintype "bidirectional"))
    )
    (net (code "36") (name "/INPUT2_16") (class "Default")
      (node (ref "IN2") (pin "16") (pinfunction "1_16") (pintype "passive"))
      (node (ref "MOS36") (pin "1") (pinfunction "GATE_1") (pintype "bidirectional"))
    )
    (net (code "37") (name "/INPUT2_17") (class "Default")
      (node (ref "IN2") (pin "17") (pinfunction "1_17") (pintype "passive"))
      (node (ref "MOS37") (pin "1") (pinfunction "GATE_1") (pintype "bidirectional"))
    )
    (net (code "38") (name "/INPUT2_18") (class "Default")
      (node (ref "IN2") (pin "18") (pinfunction "1_18") (pintype "passive"))
      (node (ref "MOS38") (pin "1") (pinfunction "GATE_1") (pintype "bidirectional"))
    )
    (net (code "39") (name "/INPUT2_19") (class "Default")
      (node (ref "IN2") (pin "19") (pinfunction "1_19") (pintype "passive"))
      (node (ref "MOS39") (pin "1") (pinfunction "GATE_1") (pintype "bidirectional"))
    )
    (net (code "40") (name "/INPUT2_20") (class "Default")
      (node (ref "IN2") (pin "20") (pinfunction "1_20") (pintype "passive"))
      (node (ref "MOS40") (pin "1") (pinfunction "GATE_1") (pintype "bidirectional"))
    )
    (net (code "41") (name "/INPUT3_1") (class "Default")
      (node (ref "IN3") (pin "1") (pinfunction "1_1") (pintype "passive"))
      (node (ref "MOS41") (pin "1") (pinfunction "GATE_1") (pintype "bidirectional"))
    )
    (net (code "42") (name "/INPUT3_2") (class "Default")
      (node (ref "IN3") (pin "2") (pinfunction "1_2") (pintype "passive"))
      (node (ref "MOS42") (pin "1") (pinfunction "GATE_1") (pintype "bidirectional"))
    )
    (net (code "43") (name "/INPUT3_3") (class "Default")
      (node (ref "IN3") (pin "3") (pinfunction "1_3") (pintype "passive"))
      (node (ref "MOS43") (pin "1") (pinfunction "GATE_1") (pintype "bidirectional"))
    )
    (net (code "44") (name "/INPUT3_4") (class "Default")
      (node (ref "IN3") (pin "4") (pinfunction "1_4") (pintype "passive"))
      (node (ref "MOS44") (pin "1") (pinfunction "GATE_1") (pintype "bidirectional"))
    )
    (net (code "45") (name "/INPUT3_5") (class "Default")
      (node (ref "IN3") (pin "5") (pinfunction "1_5") (pintype "passive"))
      (node (ref "MOS45") (pin "1") (pinfunction "GATE_1") (pintype "bidirectional"))
    )
    (net (code "46") (name "/INPUT3_6") (class "Default")
      (node (ref "IN3") (pin "6") (pinfunction "1_6") (pintype "passive"))
      (node (ref "MOS46") (pin "1") (pinfunction "GATE_1") (pintype "bidirectional"))
    )
    (net (code "47") (name "/INPUT3_7") (class "Default")
      (node (ref "IN3") (pin "7") (pinfunction "1_7") (pintype "passive"))
      (node (ref "MOS47") (pin "1") (pinfunction "GATE_1") (pintype "bidirectional"))
    )
    (net (code "48") (name "/INPUT3_8") (class "Default")
      (node (ref "IN3") (pin "8") (pinfunction "1_8") (pintype "passive"))
      (node (ref "MOS48") (pin "1") (pinfunction "GATE_1") (pintype "bidirectional"))
    )
    (net (code "49") (name "/INPUT3_9") (class "Default")
      (node (ref "IN3") (pin "9") (pinfunction "1_9") (pintype "passive"))
      (node (ref "MOS49") (pin "1") (pinfunction "GATE_1") (pintype "bidirectional"))
    )
    (net (code "50") (name "/INPUT3_10") (class "Default")
      (node (ref "IN3") (pin "10") (pinfunction "1_10") (pintype "passive"))
      (node (ref "MOS50") (pin "1") (pinfunction "GATE_1") (pintype "bidirectional"))
    )
    (net (code "51") (name "/INPUT3_11") (class "Default")
      (node (ref "IN3") (pin "11") (pinfunction "1_11") (pintype "passive"))
      (node (ref "MOS51") (pin "1") (pinfunction "GATE_1") (pintype "bidirectional"))
    )
    (net (code "52") (name "/INPUT3_12") (class "Default")
      (node (ref "IN3") (pin "12") (pinfunction "1_12") (pintype "passive"))
      (node (ref "MOS52") (pin "1") (pinfunction "GATE_1") (pintype "bidirectional"))
    )
    (net (code "53") (name "/INPUT3_13") (class "Default")
      (node (ref "IN3") (pin "13") (pinfunction "1_13") (pintype "passive"))
      (node (ref "MOS53") (pin "1") (pinfunction "GATE_1") (pintype "bidirectional"))
    )
    (net (code "54") (name "/INPUT3_14") (class "Default")
      (node (ref "IN3") (pin "14") (pinfunction "1_14") (pintype "passive"))
      (node (ref "MOS54") (pin "1") (pinfunction "GATE_1") (pintype "bidirectional"))
    )
    (net (code "55") (name "/INPUT3_15") (class "Default")
      (node (ref "IN3") (pin "15") (pinfunction "1_15") (pintype "passive"))
      (node (ref "MOS55") (pin "1") (pinfunction "GATE_1") (pintype "bidirectional"))
    )
    (net (code "56") (name "/INPUT3_16") (class "Default")
      (node (ref "IN3") (pin "16") (pinfunction "1_16") (pintype "passive"))
      (node (ref "MOS56") (pin "1") (pinfunction "GATE_1") (pintype "bidirectional"))
    )
    (net (code "57") (name "/INPUT3_17") (class "Default")
      (node (ref "IN3") (pin "17") (pinfunction "1_17") (pintype "passive"))
      (node (ref "MOS57") (pin "1") (pinfunction "GATE_1") (pintype "bidirectional"))
    )
    (net (code "58") (name "/INPUT3_18") (class "Default")
      (node (ref "IN3") (pin "18") (pinfunction "1_18") (pintype "passive"))
      (node (ref "MOS58") (pin "1") (pinfunction "GATE_1") (pintype "bidirectional"))
    )
    (net (code "59") (name "/INPUT3_19") (class "Default")
      (node (ref "IN3") (pin "19") (pinfunction "1_19") (pintype "passive"))
      (node (ref "MOS59") (pin "1") (pinfunction "GATE_1") (pintype "bidirectional"))
    )
    (net (code "60") (name "/INPUT3_20") (class "Default")
      (node (ref "IN3") (pin "20") (pinfunction "1_20") (pintype "passive"))
      (node (ref "MOS60") (pin "1") (pinfunction "GATE_1") (pintype "bidirectional"))
    )
    (net (code "61") (name "/INPUT4_1") (class "Default")
      (node (ref "IN4") (pin "1") (pinfunction "1_1") (pintype "passive"))
      (node (ref "MOS61") (pin "1") (pinfunction "GATE_1") (pintype "bidirectional"))
    )
    (net (code "62") (name "/INPUT4_2") (class "Default")
      (node (ref "IN4") (pin "2") (pinfunction "1_2") (pintype "passive"))
      (node (ref "MOS62") (pin "1") (pinfunction "GATE_1") (pintype "bidirectional"))
    )
    (net (code "63") (name "/INPUT4_3") (class "Default")
      (node (ref "IN4") (pin "3") (pinfunction "1_3") (pintype "passive"))
      (node (ref "MOS63") (pin "1") (pinfunction "GATE_1") (pintype "bidirectional"))
    )
    (net (code "64") (name "/INPUT4_4") (class "Default")
      (node (ref "IN4") (pin "4") (pinfunction "1_4") (pintype "passive"))
      (node (ref "MOS64") (pin "1") (pinfunction "GATE_1") (pintype "bidirectional"))
    )
    (net (code "65") (name "/INPUT4_5") (class "Default")
      (node (ref "IN4") (pin "5") (pinfunction "1_5") (pintype "passive"))
      (node (ref "MOS65") (pin "1") (pinfunction "GATE_1") (pintype "bidirectional"))
    )
    (net (code "66") (name "/INPUT4_6") (class "Default")
      (node (ref "IN4") (pin "6") (pinfunction "1_6") (pintype "passive"))
      (node (ref "MOS66") (pin "1") (pinfunction "GATE_1") (pintype "bidirectional"))
    )
    (net (code "67") (name "/INPUT4_7") (class "Default")
      (node (ref "IN4") (pin "7") (pinfunction "1_7") (pintype "passive"))
      (node (ref "MOS67") (pin "1") (pinfunction "GATE_1") (pintype "bidirectional"))
    )
    (net (code "68") (name "/INPUT4_8") (class "Default")
      (node (ref "IN4") (pin "8") (pinfunction "1_8") (pintype "passive"))
      (node (ref "MOS68") (pin "1") (pinfunction "GATE_1") (pintype "bidirectional"))
    )
    (net (code "69") (name "/INPUT4_9") (class "Default")
      (node (ref "IN4") (pin "9") (pinfunction "1_9") (pintype "passive"))
      (node (ref "MOS69") (pin "1") (pinfunction "GATE_1") (pintype "bidirectional"))
    )
    (net (code "70") (name "/INPUT4_10") (class "Default")
      (node (ref "IN4") (pin "10") (pinfunction "1_10") (pintype "passive"))
      (node (ref "MOS70") (pin "1") (pinfunction "GATE_1") (pintype "bidirectional"))
    )
    (net (code "71") (name "/INPUT4_11") (class "Default")
      (node (ref "IN4") (pin "11") (pinfunction "1_11") (pintype "passive"))
      (node (ref "MOS71") (pin "1") (pinfunction "GATE_1") (pintype "bidirectional"))
    )
    (net (code "72") (name "/INPUT4_12") (class "Default")
      (node (ref "IN4") (pin "12") (pinfunction "1_12") (pintype "passive"))
      (node (ref "MOS72") (pin "1") (pinfunction "GATE_1") (pintype "bidirectional"))
    )
    (net (code "73") (name "/INPUT4_13") (class "Default")
      (node (ref "IN4") (pin "13") (pinfunction "1_13") (pintype "passive"))
      (node (ref "MOS73") (pin "1") (pinfunction "GATE_1") (pintype "bidirectional"))
    )
    (net (code "74") (name "/INPUT4_14") (class "Default")
      (node (ref "IN4") (pin "14") (pinfunction "1_14") (pintype "passive"))
      (node (ref "MOS74") (pin "1") (pinfunction "GATE_1") (pintype "bidirectional"))
    )
    (net (code "75") (name "/INPUT4_15") (class "Default")
      (node (ref "IN4") (pin "15") (pinfunction "1_15") (pintype "passive"))
      (node (ref "MOS75") (pin "1") (pinfunction "GATE_1") (pintype "bidirectional"))
    )
    (net (code "76") (name "/INPUT4_16") (class "Default")
      (node (ref "IN4") (pin "16") (pinfunction "1_16") (pintype "passive"))
      (node (ref "MOS76") (pin "1") (pinfunction "GATE_1") (pintype "bidirectional"))
    )
    (net (code "77") (name "/INPUT4_17") (class "Default")
      (node (ref "IN4") (pin "17") (pinfunction "1_17") (pintype "passive"))
      (node (ref "MOS77") (pin "1") (pinfunction "GATE_1") (pintype "bidirectional"))
    )
    (net (code "78") (name "/INPUT4_18") (class "Default")
      (node (ref "IN4") (pin "18") (pinfunction "1_18") (pintype "passive"))
      (node (ref "MOS78") (pin "1") (pinfunction "GATE_1") (pintype "bidirectional"))
    )
    (net (code "79") (name "/INPUT4_19") (class "Default")
      (node (ref "IN4") (pin "19") (pinfunction "1_19") (pintype "passive"))
      (node (ref "MOS79") (pin "1") (pinfunction "GATE_1") (pintype "bidirectional"))
    )
    (net (code "80") (name "/INPUT4_20") (class "Default")
      (node (ref "IN4") (pin "20") (pinfunction "1_20") (pintype "passive"))
      (node (ref "MOS80") (pin "1") (pinfunction "GATE_1") (pintype "bidirectional"))
    )
    (net (code "81") (name "/INPUT5_1") (class "Default")
      (node (ref "IN5") (pin "1") (pinfunction "1_1") (pintype "passive"))
      (node (ref "MOS81") (pin "1") (pinfunction "GATE_1") (pintype "bidirectional"))
    )
    (net (code "82") (name "/INPUT5_2") (class "Default")
      (node (ref "IN5") (pin "2") (pinfunction "1_2") (pintype "passive"))
      (node (ref "MOS82") (pin "1") (pinfunction "GATE_1") (pintype "bidirectional"))
    )
    (net (code "83") (name "/INPUT5_3") (class "Default")
      (node (ref "IN5") (pin "3") (pinfunction "1_3") (pintype "passive"))
      (node (ref "MOS83") (pin "1") (pinfunction "GATE_1") (pintype "bidirectional"))
    )
    (net (code "84") (name "/INPUT5_4") (class "Default")
      (node (ref "IN5") (pin "4") (pinfunction "1_4") (pintype "passive"))
      (node (ref "MOS84") (pin "1") (pinfunction "GATE_1") (pintype "bidirectional"))
    )
    (net (code "85") (name "/INPUT5_5") (class "Default")
      (node (ref "IN5") (pin "5") (pinfunction "1_5") (pintype "passive"))
      (node (ref "MOS85") (pin "1") (pinfunction "GATE_1") (pintype "bidirectional"))
    )
    (net (code "86") (name "/INPUT5_6") (class "Default")
      (node (ref "IN5") (pin "6") (pinfunction "1_6") (pintype "passive"))
      (node (ref "MOS86") (pin "1") (pinfunction "GATE_1") (pintype "bidirectional"))
    )
    (net (code "87") (name "/INPUT5_7") (class "Default")
      (node (ref "IN5") (pin "7") (pinfunction "1_7") (pintype "passive"))
      (node (ref "MOS87") (pin "1") (pinfunction "GATE_1") (pintype "bidirectional"))
    )
    (net (code "88") (name "/INPUT5_8") (class "Default")
      (node (ref "IN5") (pin "8") (pinfunction "1_8") (pintype "passive"))
      (node (ref "MOS88") (pin "1") (pinfunction "GATE_1") (pintype "bidirectional"))
    )
    (net (code "89") (name "/INPUT5_9") (class "Default")
      (node (ref "IN5") (pin "9") (pinfunction "1_9") (pintype "passive"))
      (node (ref "MOS89") (pin "1") (pinfunction "GATE_1") (pintype "bidirectional"))
    )
    (net (code "90") (name "/INPUT5_10") (class "Default")
      (node (ref "IN5") (pin "10") (pinfunction "1_10") (pintype "passive"))
      (node (ref "MOS90") (pin "1") (pinfunction "GATE_1") (pintype "bidirectional"))
    )
    (net (code "91") (name "/INPUT5_11") (class "Default")
      (node (ref "IN5") (pin "11") (pinfunction "1_11") (pintype "passive"))
      (node (ref "MOS91") (pin "1") (pinfunction "GATE_1") (pintype "bidirectional"))
    )
    (net (code "92") (name "/INPUT5_12") (class "Default")
      (node (ref "IN5") (pin "12") (pinfunction "1_12") (pintype "passive"))
      (node (ref "MOS92") (pin "1") (pinfunction "GATE_1") (pintype "bidirectional"))
    )
    (net (code "93") (name "/INPUT5_13") (class "Default")
      (node (ref "IN5") (pin "13") (pinfunction "1_13") (pintype "passive"))
      (node (ref "MOS93") (pin "1") (pinfunction "GATE_1") (pintype "bidirectional"))
    )
    (net (code "94") (name "/INPUT5_14") (class "Default")
      (node (ref "IN5") (pin "14") (pinfunction "1_14") (pintype "passive"))
      (node (ref "MOS94") (pin "1") (pinfunction "GATE_1") (pintype "bidirectional"))
    )
    (net (code "95") (name "/INPUT5_15") (class "Default")
      (node (ref "IN5") (pin "15") (pinfunction "1_15") (pintype "passive"))
      (node (ref "MOS95") (pin "1") (pinfunction "GATE_1") (pintype "bidirectional"))
    )
    (net (code "96") (name "/INPUT5_16") (class "Default")
      (node (ref "IN5") (pin "16") (pinfunction "1_16") (pintype "passive"))
      (node (ref "MOS96") (pin "1") (pinfunction "GATE_1") (pintype "bidirectional"))
    )
    (net (code "97") (name "/INPUT5_17") (class "Default")
      (node (ref "IN5") (pin "17") (pinfunction "1_17") (pintype "passive"))
      (node (ref "MOS97") (pin "1") (pinfunction "GATE_1") (pintype "bidirectional"))
    )
    (net (code "98") (name "/INPUT5_18") (class "Default")
      (node (ref "IN5") (pin "18") (pinfunction "1_18") (pintype "passive"))
      (node (ref "MOS98") (pin "1") (pinfunction "GATE_1") (pintype "bidirectional"))
    )
    (net (code "99") (name "/INPUT5_19") (class "Default")
      (node (ref "IN5") (pin "19") (pinfunction "1_19") (pintype "passive"))
      (node (ref "MOS99") (pin "1") (pinfunction "GATE_1") (pintype "bidirectional"))
    )
    (net (code "100") (name "/INPUT5_20") (class "Default")
      (node (ref "IN5") (pin "20") (pinfunction "1_20") (pintype "passive"))
      (node (ref "MOS100") (pin "1") (pinfunction "GATE_1") (pintype "bidirectional"))
    )
    (net (code "101") (name "/OUTPUT1_1") (class "Default")
      (node (ref "MOS1") (pin "2") (pinfunction "SOURCE_2") (pintype "bidirectional"))
      (node (ref "OUT1") (pin "1") (pinfunction "1_1") (pintype "passive"))
    )
    (net (code "102") (name "/OUTPUT1_2") (class "Default")
      (node (ref "MOS2") (pin "2") (pinfunction "SOURCE_2") (pintype "bidirectional"))
      (node (ref "OUT1") (pin "2") (pinfunction "1_2") (pintype "passive"))
    )
    (net (code "103") (name "/OUTPUT1_3") (class "Default")
      (node (ref "MOS3") (pin "2") (pinfunction "SOURCE_2") (pintype "bidirectional"))
      (node (ref "OUT1") (pin "3") (pinfunction "1_3") (pintype "passive"))
    )
    (net (code "104") (name "/OUTPUT1_4") (class "Default")
      (node (ref "MOS4") (pin "2") (pinfunction "SOURCE_2") (pintype "bidirectional"))
      (node (ref "OUT1") (pin "4") (pinfunction "1_4") (pintype "passive"))
    )
    (net (code "105") (name "/OUTPUT1_5") (class "Default")
      (node (ref "MOS5") (pin "2") (pinfunction "SOURCE_2") (pintype "bidirectional"))
      (node (ref "OUT1") (pin "5") (pinfunction "1_5") (pintype "passive"))
    )
    (net (code "106") (name "/OUTPUT1_6") (class "Default")
      (node (ref "MOS6") (pin "2") (pinfunction "SOURCE_2") (pintype "bidirectional"))
      (node (ref "OUT1") (pin "6") (pinfunction "1_6") (pintype "passive"))
    )
    (net (code "107") (name "/OUTPUT1_7") (class "Default")
      (node (ref "MOS7") (pin "2") (pinfunction "SOURCE_2") (pintype "bidirectional"))
      (node (ref "OUT1") (pin "7") (pinfunction "1_7") (pintype "passive"))
    )
    (net (code "108") (name "/OUTPUT1_8") (class "Default")
      (node (ref "MOS8") (pin "2") (pinfunction "SOURCE_2") (pintype "bidirectional"))
      (node (ref "OUT1") (pin "8") (pinfunction "1_8") (pintype "passive"))
    )
    (net (code "109") (name "/OUTPUT1_9") (class "Default")
      (node (ref "MOS9") (pin "2") (pinfunction "SOURCE_2") (pintype "bidirectional"))
      (node (ref "OUT1") (pin "9") (pinfunction "1_9") (pintype "passive"))
    )
    (net (code "110") (name "/OUTPUT1_10") (class "Default")
      (node (ref "MOS10") (pin "2") (pinfunction "SOURCE_2") (pintype "bidirectional"))
      (node (ref "OUT1") (pin "10") (pinfunction "1_10") (pintype "passive"))
    )
    (net (code "111") (name "/OUTPUT1_11") (class "Default")
      (node (ref "MOS11") (pin "2") (pinfunction "SOURCE_2") (pintype "bidirectional"))
      (node (ref "OUT1") (pin "11") (pinfunction "1_11") (pintype "passive"))
    )
    (net (code "112") (name "/OUTPUT1_12") (class "Default")
      (node (ref "MOS12") (pin "2") (pinfunction "SOURCE_2") (pintype "bidirectional"))
      (node (ref "OUT1") (pin "12") (pinfunction "1_12") (pintype "passive"))
    )
    (net (code "113") (name "/OUTPUT1_13") (class "Default")
      (node (ref "MOS13") (pin "2") (pinfunction "SOURCE_2") (pintype "bidirectional"))
      (node (ref "OUT1") (pin "13") (pinfunction "1_13") (pintype "passive"))
    )
    (net (code "114") (name "/OUTPUT1_14") (class "Default")
      (node (ref "MOS14") (pin "2") (pinfunction "SOURCE_2") (pintype "bidirectional"))
      (node (ref "OUT1") (pin "14") (pinfunction "1_14") (pintype "passive"))
    )
    (net (code "115") (name "/OUTPUT1_15") (class "Default")
      (node (ref "MOS15") (pin "2") (pinfunction "SOURCE_2") (pintype "bidirectional"))
      (node (ref "OUT1") (pin "15") (pinfunction "1_15") (pintype "passive"))
    )
    (net (code "116") (name "/OUTPUT1_16") (class "Default")
      (node (ref "MOS16") (pin "2") (pinfunction "SOURCE_2") (pintype "bidirectional"))
      (node (ref "OUT1") (pin "16") (pinfunction "1_16") (pintype "passive"))
    )
    (net (code "117") (name "/OUTPUT1_17") (class "Default")
      (node (ref "MOS17") (pin "2") (pinfunction "SOURCE_2") (pintype "bidirectional"))
      (node (ref "OUT1") (pin "17") (pinfunction "1_17") (pintype "passive"))
    )
    (net (code "118") (name "/OUTPUT1_18") (class "Default")
      (node (ref "MOS18") (pin "2") (pinfunction "SOURCE_2") (pintype "bidirectional"))
      (node (ref "OUT1") (pin "18") (pinfunction "1_18") (pintype "passive"))
    )
    (net (code "119") (name "/OUTPUT1_19") (class "Default")
      (node (ref "MOS19") (pin "2") (pinfunction "SOURCE_2") (pintype "bidirectional"))
      (node (ref "OUT1") (pin "19") (pinfunction "1_19") (pintype "passive"))
    )
    (net (code "120") (name "/OUTPUT1_20") (class "Default")
      (node (ref "MOS20") (pin "2") (pinfunction "SOURCE_2") (pintype "bidirectional"))
      (node (ref "OUT1") (pin "20") (pinfunction "1_20") (pintype "passive"))
    )
    (net (code "121") (name "/OUTPUT2_1") (class "Default")
      (node (ref "MOS21") (pin "2") (pinfunction "SOURCE_2") (pintype "bidirectional"))
      (node (ref "OUT2") (pin "1") (pinfunction "1_1") (pintype "passive"))
    )
    (net (code "122") (name "/OUTPUT2_2") (class "Default")
      (node (ref "MOS22") (pin "2") (pinfunction "SOURCE_2") (pintype "bidirectional"))
      (node (ref "OUT2") (pin "2") (pinfunction "1_2") (pintype "passive"))
    )
    (net (code "123") (name "/OUTPUT2_3") (class "Default")
      (node (ref "MOS23") (pin "2") (pinfunction "SOURCE_2") (pintype "bidirectional"))
      (node (ref "OUT2") (pin "3") (pinfunction "1_3") (pintype "passive"))
    )
    (net (code "124") (name "/OUTPUT2_4") (class "Default")
      (node (ref "MOS24") (pin "2") (pinfunction "SOURCE_2") (pintype "bidirectional"))
      (node (ref "OUT2") (pin "4") (pinfunction "1_4") (pintype "passive"))
    )
    (net (code "125") (name "/OUTPUT2_5") (class "Default")
      (node (ref "MOS25") (pin "2") (pinfunction "SOURCE_2") (pintype "bidirectional"))
      (node (ref "OUT2") (pin "5") (pinfunction "1_5") (pintype "passive"))
    )
    (net (code "126") (name "/OUTPUT2_6") (class "Default")
      (node (ref "MOS26") (pin "2") (pinfunction "SOURCE_2") (pintype "bidirectional"))
      (node (ref "OUT2") (pin "6") (pinfunction "1_6") (pintype "passive"))
    )
    (net (code "127") (name "/OUTPUT2_7") (class "Default")
      (node (ref "MOS27") (pin "2") (pinfunction "SOURCE_2") (pintype "bidirectional"))
      (node (ref "OUT2") (pin "7") (pinfunction "1_7") (pintype "passive"))
    )
    (net (code "128") (name "/OUTPUT2_8") (class "Default")
      (node (ref "MOS28") (pin "2") (pinfunction "SOURCE_2") (pintype "bidirectional"))
      (node (ref "OUT2") (pin "8") (pinfunction "1_8") (pintype "passive"))
    )
    (net (code "129") (name "/OUTPUT2_9") (class "Default")
      (node (ref "MOS29") (pin "2") (pinfunction "SOURCE_2") (pintype "bidirectional"))
      (node (ref "OUT2") (pin "9") (pinfunction "1_9") (pintype "passive"))
    )
    (net (code "130") (name "/OUTPUT2_10") (class "Default")
      (node (ref "MOS30") (pin "2") (pinfunction "SOURCE_2") (pintype "bidirectional"))
      (node (ref "OUT2") (pin "10") (pinfunction "1_10") (pintype "passive"))
    )
    (net (code "131") (name "/OUTPUT2_11") (class "Default")
      (node (ref "MOS31") (pin "2") (pinfunction "SOURCE_2") (pintype "bidirectional"))
      (node (ref "OUT2") (pin "11") (pinfunction "1_11") (pintype "passive"))
    )
    (net (code "132") (name "/OUTPUT2_12") (class "Default")
      (node (ref "MOS32") (pin "2") (pinfunction "SOURCE_2") (pintype "bidirectional"))
      (node (ref "OUT2") (pin "12") (pinfunction "1_12") (pintype "passive"))
    )
    (net (code "133") (name "/OUTPUT2_13") (class "Default")
      (node (ref "MOS33") (pin "2") (pinfunction "SOURCE_2") (pintype "bidirectional"))
      (node (ref "OUT2") (pin "13") (pinfunction "1_13") (pintype "passive"))
    )
    (net (code "134") (name "/OUTPUT2_14") (class "Default")
      (node (ref "MOS34") (pin "2") (pinfunction "SOURCE_2") (pintype "bidirectional"))
      (node (ref "OUT2") (pin "14") (pinfunction "1_14") (pintype "passive"))
    )
    (net (code "135") (name "/OUTPUT2_15") (class "Default")
      (node (ref "MOS35") (pin "2") (pinfunction "SOURCE_2") (pintype "bidirectional"))
      (node (ref "OUT2") (pin "15") (pinfunction "1_15") (pintype "passive"))
    )
    (net (code "136") (name "/OUTPUT2_16") (class "Default")
      (node (ref "MOS36") (pin "2") (pinfunction "SOURCE_2") (pintype "bidirectional"))
      (node (ref "OUT2") (pin "16") (pinfunction "1_16") (pintype "passive"))
    )
    (net (code "137") (name "/OUTPUT2_17") (class "Default")
      (node (ref "MOS37") (pin "2") (pinfunction "SOURCE_2") (pintype "bidirectional"))
      (node (ref "OUT2") (pin "17") (pinfunction "1_17") (pintype "passive"))
    )
    (net (code "138") (name "/OUTPUT2_18") (class "Default")
      (node (ref "MOS38") (pin "2") (pinfunction "SOURCE_2") (pintype "bidirectional"))
      (node (ref "OUT2") (pin "18") (pinfunction "1_18") (pintype "passive"))
    )
    (net (code "139") (name "/OUTPUT2_19") (class "Default")
      (node (ref "MOS39") (pin "2") (pinfunction "SOURCE_2") (pintype "bidirectional"))
      (node (ref "OUT2") (pin "19") (pinfunction "1_19") (pintype "passive"))
    )
    (net (code "140") (name "/OUTPUT2_20") (class "Default")
      (node (ref "MOS40") (pin "2") (pinfunction "SOURCE_2") (pintype "bidirectional"))
      (node (ref "OUT2") (pin "20") (pinfunction "1_20") (pintype "passive"))
    )
    (net (code "141") (name "/OUTPUT3_1") (class "Default")
      (node (ref "MOS41") (pin "2") (pinfunction "SOURCE_2") (pintype "bidirectional"))
      (node (ref "OUT3") (pin "1") (pinfunction "1_1") (pintype "passive"))
    )
    (net (code "142") (name "/OUTPUT3_2") (class "Default")
      (node (ref "MOS42") (pin "2") (pinfunction "SOURCE_2") (pintype "bidirectional"))
      (node (ref "OUT3") (pin "2") (pinfunction "1_2") (pintype "passive"))
    )
    (net (code "143") (name "/OUTPUT3_3") (class "Default")
      (node (ref "MOS43") (pin "2") (pinfunction "SOURCE_2") (pintype "bidirectional"))
      (node (ref "OUT3") (pin "3") (pinfunction "1_3") (pintype "passive"))
    )
    (net (code "144") (name "/OUTPUT3_4") (class "Default")
      (node (ref "MOS44") (pin "2") (pinfunction "SOURCE_2") (pintype "bidirectional"))
      (node (ref "OUT3") (pin "4") (pinfunction "1_4") (pintype "passive"))
    )
    (net (code "145") (name "/OUTPUT3_5") (class "Default")
      (node (ref "MOS45") (pin "2") (pinfunction "SOURCE_2") (pintype "bidirectional"))
      (node (ref "OUT3") (pin "5") (pinfunction "1_5") (pintype "passive"))
    )
    (net (code "146") (name "/OUTPUT3_6") (class "Default")
      (node (ref "MOS46") (pin "2") (pinfunction "SOURCE_2") (pintype "bidirectional"))
      (node (ref "OUT3") (pin "6") (pinfunction "1_6") (pintype "passive"))
    )
    (net (code "147") (name "/OUTPUT3_7") (class "Default")
      (node (ref "MOS47") (pin "2") (pinfunction "SOURCE_2") (pintype "bidirectional"))
      (node (ref "OUT3") (pin "7") (pinfunction "1_7") (pintype "passive"))
    )
    (net (code "148") (name "/OUTPUT3_8") (class "Default")
      (node (ref "MOS48") (pin "2") (pinfunction "SOURCE_2") (pintype "bidirectional"))
      (node (ref "OUT3") (pin "8") (pinfunction "1_8") (pintype "passive"))
    )
    (net (code "149") (name "/OUTPUT3_9") (class "Default")
      (node (ref "MOS49") (pin "2") (pinfunction "SOURCE_2") (pintype "bidirectional"))
      (node (ref "OUT3") (pin "9") (pinfunction "1_9") (pintype "passive"))
    )
    (net (code "150") (name "/OUTPUT3_10") (class "Default")
      (node (ref "MOS50") (pin "2") (pinfunction "SOURCE_2") (pintype "bidirectional"))
      (node (ref "OUT3") (pin "10") (pinfunction "1_10") (pintype "passive"))
    )
    (net (code "151") (name "/OUTPUT3_11") (class "Default")
      (node (ref "MOS51") (pin "2") (pinfunction "SOURCE_2") (pintype "bidirectional"))
      (node (ref "OUT3") (pin "11") (pinfunction "1_11") (pintype "passive"))
    )
    (net (code "152") (name "/OUTPUT3_12") (class "Default")
      (node (ref "MOS52") (pin "2") (pinfunction "SOURCE_2") (pintype "bidirectional"))
      (node (ref "OUT3") (pin "12") (pinfunction "1_12") (pintype "passive"))
    )
    (net (code "153") (name "/OUTPUT3_13") (class "Default")
      (node (ref "MOS53") (pin "2") (pinfunction "SOURCE_2") (pintype "bidirectional"))
      (node (ref "OUT3") (pin "13") (pinfunction "1_13") (pintype "passive"))
    )
    (net (code "154") (name "/OUTPUT3_14") (class "Default")
      (node (ref "MOS54") (pin "2") (pinfunction "SOURCE_2") (pintype "bidirectional"))
      (node (ref "OUT3") (pin "14") (pinfunction "1_14") (pintype "passive"))
    )
    (net (code "155") (name "/OUTPUT3_15") (class "Default")
      (node (ref "MOS55") (pin "2") (pinfunction "SOURCE_2") (pintype "bidirectional"))
      (node (ref "OUT3") (pin "15") (pinfunction "1_15") (pintype "passive"))
    )
    (net (code "156") (name "/OUTPUT3_16") (class "Default")
      (node (ref "MOS56") (pin "2") (pinfunction "SOURCE_2") (pintype "bidirectional"))
      (node (ref "OUT3") (pin "16") (pinfunction "1_16") (pintype "passive"))
    )
    (net (code "157") (name "/OUTPUT3_17") (class "Default")
      (node (ref "MOS57") (pin "2") (pinfunction "SOURCE_2") (pintype "bidirectional"))
      (node (ref "OUT3") (pin "17") (pinfunction "1_17") (pintype "passive"))
    )
    (net (code "158") (name "/OUTPUT3_18") (class "Default")
      (node (ref "MOS58") (pin "2") (pinfunction "SOURCE_2") (pintype "bidirectional"))
      (node (ref "OUT3") (pin "18") (pinfunction "1_18") (pintype "passive"))
    )
    (net (code "159") (name "/OUTPUT3_19") (class "Default")
      (node (ref "MOS59") (pin "2") (pinfunction "SOURCE_2") (pintype "bidirectional"))
      (node (ref "OUT3") (pin "19") (pinfunction "1_19") (pintype "passive"))
    )
    (net (code "160") (name "/OUTPUT3_20") (class "Default")
      (node (ref "MOS60") (pin "2") (pinfunction "SOURCE_2") (pintype "bidirectional"))
      (node (ref "OUT3") (pin "20") (pinfunction "1_20") (pintype "passive"))
    )
    (net (code "161") (name "/OUTPUT4_1") (class "Default")
      (node (ref "MOS61") (pin "2") (pinfunction "SOURCE_2") (pintype "bidirectional"))
      (node (ref "OUT4") (pin "1") (pinfunction "1_1") (pintype "passive"))
    )
    (net (code "162") (name "/OUTPUT4_2") (class "Default")
      (node (ref "MOS62") (pin "2") (pinfunction "SOURCE_2") (pintype "bidirectional"))
      (node (ref "OUT4") (pin "2") (pinfunction "1_2") (pintype "passive"))
    )
    (net (code "163") (name "/OUTPUT4_3") (class "Default")
      (node (ref "MOS63") (pin "2") (pinfunction "SOURCE_2") (pintype "bidirectional"))
      (node (ref "OUT4") (pin "3") (pinfunction "1_3") (pintype "passive"))
    )
    (net (code "164") (name "/OUTPUT4_4") (class "Default")
      (node (ref "MOS64") (pin "2") (pinfunction "SOURCE_2") (pintype "bidirectional"))
      (node (ref "OUT4") (pin "4") (pinfunction "1_4") (pintype "passive"))
    )
    (net (code "165") (name "/OUTPUT4_5") (class "Default")
      (node (ref "MOS65") (pin "2") (pinfunction "SOURCE_2") (pintype "bidirectional"))
      (node (ref "OUT4") (pin "5") (pinfunction "1_5") (pintype "passive"))
    )
    (net (code "166") (name "/OUTPUT4_6") (class "Default")
      (node (ref "MOS66") (pin "2") (pinfunction "SOURCE_2") (pintype "bidirectional"))
      (node (ref "OUT4") (pin "6") (pinfunction "1_6") (pintype "passive"))
    )
    (net (code "167") (name "/OUTPUT4_7") (class "Default")
      (node (ref "MOS67") (pin "2") (pinfunction "SOURCE_2") (pintype "bidirectional"))
      (node (ref "OUT4") (pin "7") (pinfunction "1_7") (pintype "passive"))
    )
    (net (code "168") (name "/OUTPUT4_8") (class "Default")
      (node (ref "MOS68") (pin "2") (pinfunction "SOURCE_2") (pintype "bidirectional"))
      (node (ref "OUT4") (pin "8") (pinfunction "1_8") (pintype "passive"))
    )
    (net (code "169") (name "/OUTPUT4_9") (class "Default")
      (node (ref "MOS69") (pin "2") (pinfunction "SOURCE_2") (pintype "bidirectional"))
      (node (ref "OUT4") (pin "9") (pinfunction "1_9") (pintype "passive"))
    )
    (net (code "170") (name "/OUTPUT4_10") (class "Default")
      (node (ref "MOS70") (pin "2") (pinfunction "SOURCE_2") (pintype "bidirectional"))
      (node (ref "OUT4") (pin "10") (pinfunction "1_10") (pintype "passive"))
    )
    (net (code "171") (name "/OUTPUT4_11") (class "Default")
      (node (ref "MOS71") (pin "2") (pinfunction "SOURCE_2") (pintype "bidirectional"))
      (node (ref "OUT4") (pin "11") (pinfunction "1_11") (pintype "passive"))
    )
    (net (code "172") (name "/OUTPUT4_12") (class "Default")
      (node (ref "MOS72") (pin "2") (pinfunction "SOURCE_2") (pintype "bidirectional"))
      (node (ref "OUT4") (pin "12") (pinfunction "1_12") (pintype "passive"))
    )
    (net (code "173") (name "/OUTPUT4_13") (class "Default")
      (node (ref "MOS73") (pin "2") (pinfunction "SOURCE_2") (pintype "bidirectional"))
      (node (ref "OUT4") (pin "13") (pinfunction "1_13") (pintype "passive"))
    )
    (net (code "174") (name "/OUTPUT4_14") (class "Default")
      (node (ref "MOS74") (pin "2") (pinfunction "SOURCE_2") (pintype "bidirectional"))
      (node (ref "OUT4") (pin "14") (pinfunction "1_14") (pintype "passive"))
    )
    (net (code "175") (name "/OUTPUT4_15") (class "Default")
      (node (ref "MOS75") (pin "2") (pinfunction "SOURCE_2") (pintype "bidirectional"))
      (node (ref "OUT4") (pin "15") (pinfunction "1_15") (pintype "passive"))
    )
    (net (code "176") (name "/OUTPUT4_16") (class "Default")
      (node (ref "MOS76") (pin "2") (pinfunction "SOURCE_2") (pintype "bidirectional"))
      (node (ref "OUT4") (pin "16") (pinfunction "1_16") (pintype "passive"))
    )
    (net (code "177") (name "/OUTPUT4_17") (class "Default")
      (node (ref "MOS77") (pin "2") (pinfunction "SOURCE_2") (pintype "bidirectional"))
      (node (ref "OUT4") (pin "17") (pinfunction "1_17") (pintype "passive"))
    )
    (net (code "178") (name "/OUTPUT4_18") (class "Default")
      (node (ref "MOS78") (pin "2") (pinfunction "SOURCE_2") (pintype "bidirectional"))
      (node (ref "OUT4") (pin "18") (pinfunction "1_18") (pintype "passive"))
    )
    (net (code "179") (name "/OUTPUT4_19") (class "Default")
      (node (ref "MOS79") (pin "2") (pinfunction "SOURCE_2") (pintype "bidirectional"))
      (node (ref "OUT4") (pin "19") (pinfunction "1_19") (pintype "passive"))
    )
    (net (code "180") (name "/OUTPUT4_20") (class "Default")
      (node (ref "MOS80") (pin "2") (pinfunction "SOURCE_2") (pintype "bidirectional"))
      (node (ref "OUT4") (pin "20") (pinfunction "1_20") (pintype "passive"))
    )
    (net (code "181") (name "/OUTPUT5_1") (class "Default")
      (node (ref "MOS81") (pin "2") (pinfunction "SOURCE_2") (pintype "bidirectional"))
      (node (ref "OUT5") (pin "1") (pinfunction "1_1") (pintype "passive"))
    )
    (net (code "182") (name "/OUTPUT5_2") (class "Default")
      (node (ref "MOS82") (pin "2") (pinfunction "SOURCE_2") (pintype "bidirectional"))
      (node (ref "OUT5") (pin "2") (pinfunction "1_2") (pintype "passive"))
    )
    (net (code "183") (name "/OUTPUT5_3") (class "Default")
      (node (ref "MOS83") (pin "2") (pinfunction "SOURCE_2") (pintype "bidirectional"))
      (node (ref "OUT5") (pin "3") (pinfunction "1_3") (pintype "passive"))
    )
    (net (code "184") (name "/OUTPUT5_4") (class "Default")
      (node (ref "MOS84") (pin "2") (pinfunction "SOURCE_2") (pintype "bidirectional"))
      (node (ref "OUT5") (pin "4") (pinfunction "1_4") (pintype "passive"))
    )
    (net (code "185") (name "/OUTPUT5_5") (class "Default")
      (node (ref "MOS85") (pin "2") (pinfunction "SOURCE_2") (pintype "bidirectional"))
      (node (ref "OUT5") (pin "5") (pinfunction "1_5") (pintype "passive"))
    )
    (net (code "186") (name "/OUTPUT5_6") (class "Default")
      (node (ref "MOS86") (pin "2") (pinfunction "SOURCE_2") (pintype "bidirectional"))
      (node (ref "OUT5") (pin "6") (pinfunction "1_6") (pintype "passive"))
    )
    (net (code "187") (name "/OUTPUT5_7") (class "Default")
      (node (ref "MOS87") (pin "2") (pinfunction "SOURCE_2") (pintype "bidirectional"))
      (node (ref "OUT5") (pin "7") (pinfunction "1_7") (pintype "passive"))
    )
    (net (code "188") (name "/OUTPUT5_8") (class "Default")
      (node (ref "MOS88") (pin "2") (pinfunction "SOURCE_2") (pintype "bidirectional"))
      (node (ref "OUT5") (pin "8") (pinfunction "1_8") (pintype "passive"))
    )
    (net (code "189") (name "/OUTPUT5_9") (class "Default")
      (node (ref "MOS89") (pin "2") (pinfunction "SOURCE_2") (pintype "bidirectional"))
      (node (ref "OUT5") (pin "9") (pinfunction "1_9") (pintype "passive"))
    )
    (net (code "190") (name "/OUTPUT5_10") (class "Default")
      (node (ref "MOS90") (pin "2") (pinfunction "SOURCE_2") (pintype "bidirectional"))
      (node (ref "OUT5") (pin "10") (pinfunction "1_10") (pintype "passive"))
    )
    (net (code "191") (name "/OUTPUT5_11") (class "Default")
      (node (ref "MOS91") (pin "2") (pinfunction "SOURCE_2") (pintype "bidirectional"))
      (node (ref "OUT5") (pin "11") (pinfunction "1_11") (pintype "passive"))
    )
    (net (code "192") (name "/OUTPUT5_12") (class "Default")
      (node (ref "MOS92") (pin "2") (pinfunction "SOURCE_2") (pintype "bidirectional"))
      (node (ref "OUT5") (pin "12") (pinfunction "1_12") (pintype "passive"))
    )
    (net (code "193") (name "/OUTPUT5_13") (class "Default")
      (node (ref "MOS93") (pin "2") (pinfunction "SOURCE_2") (pintype "bidirectional"))
      (node (ref "OUT5") (pin "13") (pinfunction "1_13") (pintype "passive"))
    )
    (net (code "194") (name "/OUTPUT5_14") (class "Default")
      (node (ref "MOS94") (pin "2") (pinfunction "SOURCE_2") (pintype "bidirectional"))
      (node (ref "OUT5") (pin "14") (pinfunction "1_14") (pintype "passive"))
    )
    (net (code "195") (name "/OUTPUT5_15") (class "Default")
      (node (ref "MOS95") (pin "2") (pinfunction "SOURCE_2") (pintype "bidirectional"))
      (node (ref "OUT5") (pin "15") (pinfunction "1_15") (pintype "passive"))
    )
    (net (code "196") (name "/OUTPUT5_16") (class "Default")
      (node (ref "MOS96") (pin "2") (pinfunction "SOURCE_2") (pintype "bidirectional"))
      (node (ref "OUT5") (pin "16") (pinfunction "1_16") (pintype "passive"))
    )
    (net (code "197") (name "/OUTPUT5_17") (class "Default")
      (node (ref "MOS97") (pin "2") (pinfunction "SOURCE_2") (pintype "bidirectional"))
      (node (ref "OUT5") (pin "17") (pinfunction "1_17") (pintype "passive"))
    )
    (net (code "198") (name "/OUTPUT5_18") (class "Default")
      (node (ref "MOS98") (pin "2") (pinfunction "SOURCE_2") (pintype "bidirectional"))
      (node (ref "OUT5") (pin "18") (pinfunction "1_18") (pintype "passive"))
    )
    (net (code "199") (name "/OUTPUT5_19") (class "Default")
      (node (ref "MOS99") (pin "2") (pinfunction "SOURCE_2") (pintype "bidirectional"))
      (node (ref "OUT5") (pin "19") (pinfunction "1_19") (pintype "passive"))
    )
    (net (code "200") (name "/OUTPUT5_20") (class "Default")
      (node (ref "MOS100") (pin "2") (pinfunction "SOURCE_2") (pintype "bidirectional"))
      (node (ref "OUT5") (pin "20") (pinfunction "1_20") (pintype "passive"))
    )
    (net (code "201") (name "/VIN") (class "Default")
      (node (ref "JP1") (pin "1") (pinfunction "1_1") (pintype "passive"))
      (node (ref "JP2") (pin "1") (pinfunction "1_1") (pintype "passive"))
      (node (ref "LDO") (pin "IN") (pinfunction "IN_IN") (pintype "bidirectional"))
      (node (ref "LDO_C1") (pin "1") (pinfunction "1_1") (pintype "passive"))
      (node (ref "LDO_R3") (pin "1") (pinfunction "1_1") (pintype "passive"))
    )
    (net (code "202") (name "/VOUT") (class "Default")
      (node (ref "LDO") (pin "OUT") (pinfunction "OUT_OUT") (pintype "bidirectional"))
      (node (ref "LDO_C2") (pin "1") (pinfunction "1_1") (pintype "passive"))
      (node (ref "LDO_R1") (pin "2") (pinfunction "2_2") (pintype "passive"))
      (node (ref "R1") (pin "1") (pinfunction "1_1") (pintype "passive"))
      (node (ref "R10") (pin "1") (pinfunction "1_1") (pintype "passive"))
      (node (ref "R100") (pin "1") (pinfunction "1_1") (pintype "passive"))
      (node (ref "R11") (pin "1") (pinfunction "1_1") (pintype "passive"))
      (node (ref "R12") (pin "1") (pinfunction "1_1") (pintype "passive"))
      (node (ref "R13") (pin "1") (pinfunction "1_1") (pintype "passive"))
      (node (ref "R14") (pin "1") (pinfunction "1_1") (pintype "passive"))
      (node (ref "R15") (pin "1") (pinfunction "1_1") (pintype "passive"))
      (node (ref "R16") (pin "1") (pinfunction "1_1") (pintype "passive"))
      (node (ref "R17") (pin "1") (pinfunction "1_1") (pintype "passive"))
      (node (ref "R18") (pin "1") (pinfunction "1_1") (pintype "passive"))
      (node (ref "R19") (pin "1") (pinfunction "1_1") (pintype "passive"))
      (node (ref "R2") (pin "1") (pinfunction "1_1") (pintype "passive"))
      (node (ref "R20") (pin "1") (pinfunction "1_1") (pintype "passive"))
      (node (ref "R21") (pin "1") (pinfunction "1_1") (pintype "passive"))
      (node (ref "R22") (pin "1") (pinfunction "1_1") (pintype "passive"))
      (node (ref "R23") (pin "1") (pinfunction "1_1") (pintype "passive"))
      (node (ref "R24") (pin "1") (pinfunction "1_1") (pintype "passive"))
      (node (ref "R25") (pin "1") (pinfunction "1_1") (pintype "passive"))
      (node (ref "R26") (pin "1") (pinfunction "1_1") (pintype "passive"))
      (node (ref "R27") (pin "1") (pinfunction "1_1") (pintype "passive"))
      (node (ref "R28") (pin "1") (pinfunction "1_1") (pintype "passive"))
      (node (ref "R29") (pin "1") (pinfunction "1_1") (pintype "passive"))
      (node (ref "R3") (pin "1") (pinfunction "1_1") (pintype "passive"))
      (node (ref "R30") (pin "1") (pinfunction "1_1") (pintype "passive"))
      (node (ref "R31") (pin "1") (pinfunction "1_1") (pintype "passive"))
      (node (ref "R32") (pin "1") (pinfunction "1_1") (pintype "passive"))
      (node (ref "R33") (pin "1") (pinfunction "1_1") (pintype "passive"))
      (node (ref "R34") (pin "1") (pinfunction "1_1") (pintype "passive"))
      (node (ref "R35") (pin "1") (pinfunction "1_1") (pintype "passive"))
      (node (ref "R36") (pin "1") (pinfunction "1_1") (pintype "passive"))
      (node (ref "R37") (pin "1") (pinfunction "1_1") (pintype "passive"))
      (node (ref "R38") (pin "1") (pinfunction "1_1") (pintype "passive"))
      (node (ref "R39") (pin "1") (pinfunction "1_1") (pintype "passive"))
      (node (ref "R4") (pin "1") (pinfunction "1_1") (pintype "passive"))
      (node (ref "R40") (pin "1") (pinfunction "1_1") (pintype "passive"))
      (node (ref "R41") (pin "1") (pinfunction "1_1") (pintype "passive"))
      (node (ref "R42") (pin "1") (pinfunction "1_1") (pintype "passive"))
      (node (ref "R43") (pin "1") (pinfunction "1_1") (pintype "passive"))
      (node (ref "R44") (pin "1") (pinfunction "1_1") (pintype "passive"))
      (node (ref "R45") (pin "1") (pinfunction "1_1") (pintype "passive"))
      (node (ref "R46") (pin "1") (pinfunction "1_1") (pintype "passive"))
      (node (ref "R47") (pin "1") (pinfunction "1_1") (pintype "passive"))
      (node (ref "R48") (pin "1") (pinfunction "1_1") (pintype "passive"))
      (node (ref "R49") (pin "1") (pinfunction "1_1") (pintype "passive"))
      (node (ref "R5") (pin "1") (pinfunction "1_1") (pintype "passive"))
      (node (ref "R50") (pin "1") (pinfunction "1_1") (pintype "passive"))
      (node (ref "R51") (pin "1") (pinfunction "1_1") (pintype "passive"))
      (node (ref "R52") (pin "1") (pinfunction "1_1") (pintype "passive"))
      (node (ref "R53") (pin "1") (pinfunction "1_1") (pintype "passive"))
      (node (ref "R54") (pin "1") (pinfunction "1_1") (pintype "passive"))
      (node (ref "R55") (pin "1") (pinfunction "1_1") (pintype "passive"))
      (node (ref "R56") (pin "1") (pinfunction "1_1") (pintype "passive"))
      (node (ref "R57") (pin "1") (pinfunction "1_1") (pintype "passive"))
      (node (ref "R58") (pin "1") (pinfunction "1_1") (pintype "passive"))
      (node (ref "R59") (pin "1") (pinfunction "1_1") (pintype "passive"))
      (node (ref "R6") (pin "1") (pinfunction "1_1") (pintype "passive"))
      (node (ref "R60") (pin "1") (pinfunction "1_1") (pintype "passive"))
      (node (ref "R61") (pin "1") (pinfunction "1_1") (pintype "passive"))
      (node (ref "R62") (pin "1") (pinfunction "1_1") (pintype "passive"))
      (node (ref "R63") (pin "1") (pinfunction "1_1") (pintype "passive"))
      (node (ref "R64") (pin "1") (pinfunction "1_1") (pintype "passive"))
      (node (ref "R65") (pin "1") (pinfunction "1_1") (pintype "passive"))
      (node (ref "R66") (pin "1") (pinfunction "1_1") (pintype "passive"))
      (node (ref "R67") (pin "1") (pinfunction "1_1") (pintype "passive"))
      (node (ref "R68") (pin "1") (pinfunction "1_1") (pintype "passive"))
      (node (ref "R69") (pin "1") (pinfunction "1_1") (pintype "passive"))
      (node (ref "R7") (pin "1") (pinfunction "1_1") (pintype "passive"))
      (node (ref "R70") (pin "1") (pinfunction "1_1") (pintype "passive"))
      (node (ref "R71") (pin "1") (pinfunction "1_1") (pintype "passive"))
      (node (ref "R72") (pin "1") (pinfunction "1_1") (pintype "passive"))
      (node (ref "R73") (pin "1") (pinfunction "1_1") (pintype "passive"))
      (node (ref "R74") (pin "1") (pinfunction "1_1") (pintype "passive"))
      (node (ref "R75") (pin "1") (pinfunction "1_1") (pintype "passive"))
      (node (ref "R76") (pin "1") (pinfunction "1_1") (pintype "passive"))
      (node (ref "R77") (pin "1") (pinfunction "1_1") (pintype "passive"))
      (node (ref "R78") (pin "1") (pinfunction "1_1") (pintype "passive"))
      (node (ref "R79") (pin "1") (pinfunction "1_1") (pintype "passive"))
      (node (ref "R8") (pin "1") (pinfunction "1_1") (pintype "passive"))
      (node (ref "R80") (pin "1") (pinfunction "1_1") (pintype "passive"))
      (node (ref "R81") (pin "1") (pinfunction "1_1") (pintype "passive"))
      (node (ref "R82") (pin "1") (pinfunction "1_1") (pintype "passive"))
      (node (ref "R83") (pin "1") (pinfunction "1_1") (pintype "passive"))
      (node (ref "R84") (pin "1") (pinfunction "1_1") (pintype "passive"))
      (node (ref "R85") (pin "1") (pinfunction "1_1") (pintype "passive"))
      (node (ref "R86") (pin "1") (pinfunction "1_1") (pintype "passive"))
      (node (ref "R87") (pin "1") (pinfunction "1_1") (pintype "passive"))
      (node (ref "R88") (pin "1") (pinfunction "1_1") (pintype "passive"))
      (node (ref "R89") (pin "1") (pinfunction "1_1") (pintype "passive"))
      (node (ref "R9") (pin "1") (pinfunction "1_1") (pintype "passive"))
      (node (ref "R90") (pin "1") (pinfunction "1_1") (pintype "passive"))
      (node (ref "R91") (pin "1") (pinfunction "1_1") (pintype "passive"))
      (node (ref "R92") (pin "1") (pinfunction "1_1") (pintype "passive"))
      (node (ref "R93") (pin "1") (pinfunction "1_1") (pintype "passive"))
      (node (ref "R94") (pin "1") (pinfunction "1_1") (pintype "passive"))
      (node (ref "R95") (pin "1") (pinfunction "1_1") (pintype "passive"))
      (node (ref "R96") (pin "1") (pinfunction "1_1") (pintype "passive"))
      (node (ref "R97") (pin "1") (pinfunction "1_1") (pintype "passive"))
      (node (ref "R98") (pin "1") (pinfunction "1_1") (pintype "passive"))
      (node (ref "R99") (pin "1") (pinfunction "1_1") (pintype "passive"))
    )
    (net (code "203") (name "GND") (class "Default")
      (node (ref "JP1") (pin "2") (pinfunction "2_2") (pintype "passive"))
      (node (ref "JP2") (pin "2") (pinfunction "2_2") (pintype "passive"))
      (node (ref "LDO") (pin "DAP") (pinfunction "DAP_DAP") (pintype "bidirectional"))
      (node (ref "LDO") (pin "GND") (pinfunction "GND_GND") (pintype "bidirectional"))
      (node (ref "LDO_C1") (pin "2") (pinfunction "2_2") (pintype "passive"))
      (node (ref "LDO_C2") (pin "2") (pinfunction "2_2") (pintype "passive"))
      (node (ref "LDO_R2") (pin "1") (pinfunction "1_1") (pintype "passive"))
    )
    (net (code "204") (name "Net-(LDO-PadADJ)") (class "Default")
      (node (ref "LDO") (pin "ADJ") (pinfunction "ADJ_ADJ") (pintype "bidirectional"))
      (node (ref "LDO_R1") (pin "1") (pinfunction "1_1") (pintype "passive"))
      (node (ref "LDO_R2") (pin "2") (pinfunction "2_2") (pintype "passive"))
    )
    (net (code "205") (name "Net-(LDO-PadEN)") (class "Default")
      (node (ref "LDO") (pin "EN") (pinfunction "EN_EN") (pintype "bidirectional"))
      (node (ref "LDO_R3") (pin "2") (pinfunction "2_2") (pintype "passive"))
    )
    (net (code "206") (name "Net-(MOS1-DRAIN)") (class "Default")
      (node (ref "MOS1") (pin "3") (pinfunction "DRAIN_3") (pintype "bidirectional"))
      (node (ref "R1") (pin "2") (pinfunction "2_2") (pintype "passive"))
    )
    (net (code "207") (name "Net-(MOS2-DRAIN)") (class "Default")
      (node (ref "MOS2") (pin "3") (pinfunction "DRAIN_3") (pintype "bidirectional"))
      (node (ref "R2") (pin "2") (pinfunction "2_2") (pintype "passive"))
    )
    (net (code "208") (name "Net-(MOS3-DRAIN)") (class "Default")
      (node (ref "MOS3") (pin "3") (pinfunction "DRAIN_3") (pintype "bidirectional"))
      (node (ref "R3") (pin "2") (pinfunction "2_2") (pintype "passive"))
    )
    (net (code "209") (name "Net-(MOS4-DRAIN)") (class "Default")
      (node (ref "MOS4") (pin "3") (pinfunction "DRAIN_3") (pintype "bidirectional"))
      (node (ref "R4") (pin "2") (pinfunction "2_2") (pintype "passive"))
    )
    (net (code "210") (name "Net-(MOS5-DRAIN)") (class "Default")
      (node (ref "MOS5") (pin "3") (pinfunction "DRAIN_3") (pintype "bidirectional"))
      (node (ref "R5") (pin "2") (pinfunction "2_2") (pintype "passive"))
    )
    (net (code "211") (name "Net-(MOS6-DRAIN)") (class "Default")
      (node (ref "MOS6") (pin "3") (pinfunction "DRAIN_3") (pintype "bidirectional"))
      (node (ref "R6") (pin "2") (pinfunction "2_2") (pintype "passive"))
    )
    (net (code "212") (name "Net-(MOS7-DRAIN)") (class "Default")
      (node (ref "MOS7") (pin "3") (pinfunction "DRAIN_3") (pintype "bidirectional"))
      (node (ref "R7") (pin "2") (pinfunction "2_2") (pintype "passive"))
    )
    (net (code "213") (name "Net-(MOS8-DRAIN)") (class "Default")
      (node (ref "MOS8") (pin "3") (pinfunction "DRAIN_3") (pintype "bidirectional"))
      (node (ref "R8") (pin "2") (pinfunction "2_2") (pintype "passive"))
    )
    (net (code "214") (name "Net-(MOS9-DRAIN)") (class "Default")
      (node (ref "MOS9") (pin "3") (pinfunction "DRAIN_3") (pintype "bidirectional"))
      (node (ref "R9") (pin "2") (pinfunction "2_2") (pintype "passive"))
    )
    (net (code "215") (name "Net-(MOS10-DRAIN)") (class "Default")
      (node (ref "MOS10") (pin "3") (pinfunction "DRAIN_3") (pintype "bidirectional"))
      (node (ref "R10") (pin "2") (pinfunction "2_2") (pintype "passive"))
    )
    (net (code "216") (name "Net-(MOS11-DRAIN)") (class "Default")
      (node (ref "MOS11") (pin "3") (pinfunction "DRAIN_3") (pintype "bidirectional"))
      (node (ref "R11") (pin "2") (pinfunction "2_2") (pintype "passive"))
    )
    (net (code "217") (name "Net-(MOS12-DRAIN)") (class "Default")
      (node (ref "MOS12") (pin "3") (pinfunction "DRAIN_3") (pintype "bidirectional"))
      (node (ref "R12") (pin "2") (pinfunction "2_2") (pintype "passive"))
    )
    (net (code "218") (name "Net-(MOS13-DRAIN)") (class "Default")
      (node (ref "MOS13") (pin "3") (pinfunction "DRAIN_3") (pintype "bidirectional"))
      (node (ref "R13") (pin "2") (pinfunction "2_2") (pintype "passive"))
    )
    (net (code "219") (name "Net-(MOS14-DRAIN)") (class "Default")
      (node (ref "MOS14") (pin "3") (pinfunction "DRAIN_3") (pintype "bidirectional"))
      (node (ref "R14") (pin "2") (pinfunction "2_2") (pintype "passive"))
    )
    (net (code "220") (name "Net-(MOS15-DRAIN)") (class "Default")
      (node (ref "MOS15") (pin "3") (pinfunction "DRAIN_3") (pintype "bidirectional"))
      (node (ref "R15") (pin "2") (pinfunction "2_2") (pintype "passive"))
    )
    (net (code "221") (name "Net-(MOS16-DRAIN)") (class "Default")
      (node (ref "MOS16") (pin "3") (pinfunction "DRAIN_3") (pintype "bidirectional"))
      (node (ref "R16") (pin "2") (pinfunction "2_2") (pintype "passive"))
    )
    (net (code "222") (name "Net-(MOS17-DRAIN)") (class "Default")
      (node (ref "MOS17") (pin "3") (pinfunction "DRAIN_3") (pintype "bidirectional"))
      (node (ref "R17") (pin "2") (pinfunction "2_2") (pintype "passive"))
    )
    (net (code "223") (name "Net-(MOS18-DRAIN)") (class "Default")
      (node (ref "MOS18") (pin "3") (pinfunction "DRAIN_3") (pintype "bidirectional"))
      (node (ref "R18") (pin "2") (pinfunction "2_2") (pintype "passive"))
    )
    (net (code "224") (name "Net-(MOS19-DRAIN)") (class "Default")
      (node (ref "MOS19") (pin "3") (pinfunction "DRAIN_3") (pintype "bidirectional"))
      (node (ref "R19") (pin "2") (pinfunction "2_2") (pintype "passive"))
    )
    (net (code "225") (name "Net-(MOS20-DRAIN)") (class "Default")
      (node (ref "MOS20") (pin "3") (pinfunction "DRAIN_3") (pintype "bidirectional"))
      (node (ref "R20") (pin "2") (pinfunction "2_2") (pintype "passive"))
    )
    (net (code "226") (name "Net-(MOS21-DRAIN)") (class "Default")
      (node (ref "MOS21") (pin "3") (pinfunction "DRAIN_3") (pintype "bidirectional"))
      (node (ref "R21") (pin "2") (pinfunction "2_2") (pintype "passive"))
    )
    (net (code "227") (name "Net-(MOS22-DRAIN)") (class "Default")
      (node (ref "MOS22") (pin "3") (pinfunction "DRAIN_3") (pintype "bidirectional"))
      (node (ref "R22") (pin "2") (pinfunction "2_2") (pintype "passive"))
    )
    (net (code "228") (name "Net-(MOS23-DRAIN)") (class "Default")
      (node (ref "MOS23") (pin "3") (pinfunction "DRAIN_3") (pintype "bidirectional"))
      (node (ref "R23") (pin "2") (pinfunction "2_2") (pintype "passive"))
    )
    (net (code "229") (name "Net-(MOS24-DRAIN)") (class "Default")
      (node (ref "MOS24") (pin "3") (pinfunction "DRAIN_3") (pintype "bidirectional"))
      (node (ref "R24") (pin "2") (pinfunction "2_2") (pintype "passive"))
    )
    (net (code "230") (name "Net-(MOS25-DRAIN)") (class "Default")
      (node (ref "MOS25") (pin "3") (pinfunction "DRAIN_3") (pintype "bidirectional"))
      (node (ref "R25") (pin "2") (pinfunction "2_2") (pintype "passive"))
    )
    (net (code "231") (name "Net-(MOS26-DRAIN)") (class "Default")
      (node (ref "MOS26") (pin "3") (pinfunction "DRAIN_3") (pintype "bidirectional"))
      (node (ref "R26") (pin "2") (pinfunction "2_2") (pintype "passive"))
    )
    (net (code "232") (name "Net-(MOS27-DRAIN)") (class "Default")
      (node (ref "MOS27") (pin "3") (pinfunction "DRAIN_3") (pintype "bidirectional"))
      (node (ref "R27") (pin "2") (pinfunction "2_2") (pintype "passive"))
    )
    (net (code "233") (name "Net-(MOS28-DRAIN)") (class "Default")
      (node (ref "MOS28") (pin "3") (pinfunction "DRAIN_3") (pintype "bidirectional"))
      (node (ref "R28") (pin "2") (pinfunction "2_2") (pintype "passive"))
    )
    (net (code "234") (name "Net-(MOS29-DRAIN)") (class "Default")
      (node (ref "MOS29") (pin "3") (pinfunction "DRAIN_3") (pintype "bidirectional"))
      (node (ref "R29") (pin "2") (pinfunction "2_2") (pintype "passive"))
    )
    (net (code "235") (name "Net-(MOS30-DRAIN)") (class "Default")
      (node (ref "MOS30") (pin "3") (pinfunction "DRAIN_3") (pintype "bidirectional"))
      (node (ref "R30") (pin "2") (pinfunction "2_2") (pintype "passive"))
    )
    (net (code "236") (name "Net-(MOS31-DRAIN)") (class "Default")
      (node (ref "MOS31") (pin "3") (pinfunction "DRAIN_3") (pintype "bidirectional"))
      (node (ref "R31") (pin "2") (pinfunction "2_2") (pintype "passive"))
    )
    (net (code "237") (name "Net-(MOS32-DRAIN)") (class "Default")
      (node (ref "MOS32") (pin "3") (pinfunction "DRAIN_3") (pintype "bidirectional"))
      (node (ref "R32") (pin "2") (pinfunction "2_2") (pintype "passive"))
    )
    (net (code "238") (name "Net-(MOS33-DRAIN)") (class "Default")
      (node (ref "MOS33") (pin "3") (pinfunction "DRAIN_3") (pintype "bidirectional"))
      (node (ref "R33") (pin "2") (pinfunction "2_2") (pintype "passive"))
    )
    (net (code "239") (name "Net-(MOS34-DRAIN)") (class "Default")
      (node (ref "MOS34") (pin "3") (pinfunction "DRAIN_3") (pintype "bidirectional"))
      (node (ref "R34") (pin "2") (pinfunction "2_2") (pintype "passive"))
    )
    (net (code "240") (name "Net-(MOS35-DRAIN)") (class "Default")
      (node (ref "MOS35") (pin "3") (pinfunction "DRAIN_3") (pintype "bidirectional"))
      (node (ref "R35") (pin "2") (pinfunction "2_2") (pintype "passive"))
    )
    (net (code "241") (name "Net-(MOS36-DRAIN)") (class "Default")
      (node (ref "MOS36") (pin "3") (pinfunction "DRAIN_3") (pintype "bidirectional"))
      (node (ref "R36") (pin "2") (pinfunction "2_2") (pintype "passive"))
    )
    (net (code "242") (name "Net-(MOS37-DRAIN)") (class "Default")
      (node (ref "MOS37") (pin "3") (pinfunction "DRAIN_3") (pintype "bidirectional"))
      (node (ref "R37") (pin "2") (pinfunction "2_2") (pintype "passive"))
    )
    (net (code "243") (name "Net-(MOS38-DRAIN)") (class "Default")
      (node (ref "MOS38") (pin "3") (pinfunction "DRAIN_3") (pintype "bidirectional"))
      (node (ref "R38") (pin "2") (pinfunction "2_2") (pintype "passive"))
    )
    (net (code "244") (name "Net-(MOS39-DRAIN)") (class "Default")
      (node (ref "MOS39") (pin "3") (pinfunction "DRAIN_3") (pintype "bidirectional"))
      (node (ref "R39") (pin "2") (pinfunction "2_2") (pintype "passive"))
    )
    (net (code "245") (name "Net-(MOS40-DRAIN)") (class "Default")
      (node (ref "MOS40") (pin "3") (pinfunction "DRAIN_3") (pintype "bidirectional"))
      (node (ref "R40") (pin "2") (pinfunction "2_2") (pintype "passive"))
    )
    (net (code "246") (name "Net-(MOS41-DRAIN)") (class "Default")
      (node (ref "MOS41") (pin "3") (pinfunction "DRAIN_3") (pintype "bidirectional"))
      (node (ref "R41") (pin "2") (pinfunction "2_2") (pintype "passive"))
    )
    (net (code "247") (name "Net-(MOS42-DRAIN)") (class "Default")
      (node (ref "MOS42") (pin "3") (pinfunction "DRAIN_3") (pintype "bidirectional"))
      (node (ref "R42") (pin "2") (pinfunction "2_2") (pintype "passive"))
    )
    (net (code "248") (name "Net-(MOS43-DRAIN)") (class "Default")
      (node (ref "MOS43") (pin "3") (pinfunction "DRAIN_3") (pintype "bidirectional"))
      (node (ref "R43") (pin "2") (pinfunction "2_2") (pintype "passive"))
    )
    (net (code "249") (name "Net-(MOS44-DRAIN)") (class "Default")
      (node (ref "MOS44") (pin "3") (pinfunction "DRAIN_3") (pintype "bidirectional"))
      (node (ref "R44") (pin "2") (pinfunction "2_2") (pintype "passive"))
    )
    (net (code "250") (name "Net-(MOS45-DRAIN)") (class "Default")
      (node (ref "MOS45") (pin "3") (pinfunction "DRAIN_3") (pintype "bidirectional"))
      (node (ref "R45") (pin "2") (pinfunction "2_2") (pintype "passive"))
    )
    (net (code "251") (name "Net-(MOS46-DRAIN)") (class "Default")
      (node (ref "MOS46") (pin "3") (pinfunction "DRAIN_3") (pintype "bidirectional"))
      (node (ref "R46") (pin "2") (pinfunction "2_2") (pintype "passive"))
    )
    (net (code "252") (name "Net-(MOS47-DRAIN)") (class "Default")
      (node (ref "MOS47") (pin "3") (pinfunction "DRAIN_3") (pintype "bidirectional"))
      (node (ref "R47") (pin "2") (pinfunction "2_2") (pintype "passive"))
    )
    (net (code "253") (name "Net-(MOS48-DRAIN)") (class "Default")
      (node (ref "MOS48") (pin "3") (pinfunction "DRAIN_3") (pintype "bidirectional"))
      (node (ref "R48") (pin "2") (pinfunction "2_2") (pintype "passive"))
    )
    (net (code "254") (name "Net-(MOS49-DRAIN)") (class "Default")
      (node (ref "MOS49") (pin "3") (pinfunction "DRAIN_3") (pintype "bidirectional"))
      (node (ref "R49") (pin "2") (pinfunction "2_2") (pintype "passive"))
    )
    (net (code "255") (name "Net-(MOS50-DRAIN)") (class "Default")
      (node (ref "MOS50") (pin "3") (pinfunction "DRAIN_3") (pintype "bidirectional"))
      (node (ref "R50") (pin "2") (pinfunction "2_2") (pintype "passive"))
    )
    (net (code "256") (name "Net-(MOS51-DRAIN)") (class "Default")
      (node (ref "MOS51") (pin "3") (pinfunction "DRAIN_3") (pintype "bidirectional"))
      (node (ref "R51") (pin "2") (pinfunction "2_2") (pintype "passive"))
    )
    (net (code "257") (name "Net-(MOS52-DRAIN)") (class "Default")
      (node (ref "MOS52") (pin "3") (pinfunction "DRAIN_3") (pintype "bidirectional"))
      (node (ref "R52") (pin "2") (pinfunction "2_2") (pintype "passive"))
    )
    (net (code "258") (name "Net-(MOS53-DRAIN)") (class "Default")
      (node (ref "MOS53") (pin "3") (pinfunction "DRAIN_3") (pintype "bidirectional"))
      (node (ref "R53") (pin "2") (pinfunction "2_2") (pintype "passive"))
    )
    (net (code "259") (name "Net-(MOS54-DRAIN)") (class "Default")
      (node (ref "MOS54") (pin "3") (pinfunction "DRAIN_3") (pintype "bidirectional"))
      (node (ref "R54") (pin "2") (pinfunction "2_2") (pintype "passive"))
    )
    (net (code "260") (name "Net-(MOS55-DRAIN)") (class "Default")
      (node (ref "MOS55") (pin "3") (pinfunction "DRAIN_3") (pintype "bidirectional"))
      (node (ref "R55") (pin "2") (pinfunction "2_2") (pintype "passive"))
    )
    (net (code "261") (name "Net-(MOS56-DRAIN)") (class "Default")
      (node (ref "MOS56") (pin "3") (pinfunction "DRAIN_3") (pintype "bidirectional"))
      (node (ref "R56") (pin "2") (pinfunction "2_2") (pintype "passive"))
    )
    (net (code "262") (name "Net-(MOS57-DRAIN)") (class "Default")
      (node (ref "MOS57") (pin "3") (pinfunction "DRAIN_3") (pintype "bidirectional"))
      (node (ref "R57") (pin "2") (pinfunction "2_2") (pintype "passive"))
    )
    (net (code "263") (name "Net-(MOS58-DRAIN)") (class "Default")
      (node (ref "MOS58") (pin "3") (pinfunction "DRAIN_3") (pintype "bidirectional"))
      (node (ref "R58") (pin "2") (pinfunction "2_2") (pintype "passive"))
    )
    (net (code "264") (name "Net-(MOS59-DRAIN)") (class "Default")
      (node (ref "MOS59") (pin "3") (pinfunction "DRAIN_3") (pintype "bidirectional"))
      (node (ref "R59") (pin "2") (pinfunction "2_2") (pintype "passive"))
    )
    (net (code "265") (name "Net-(MOS60-DRAIN)") (class "Default")
      (node (ref "MOS60") (pin "3") (pinfunction "DRAIN_3") (pintype "bidirectional"))
      (node (ref "R60") (pin "2") (pinfunction "2_2") (pintype "passive"))
    )
    (net (code "266") (name "Net-(MOS61-DRAIN)") (class "Default")
      (node (ref "MOS61") (pin "3") (pinfunction "DRAIN_3") (pintype "bidirectional"))
      (node (ref "R61") (pin "2") (pinfunction "2_2") (pintype "passive"))
    )
    (net (code "267") (name "Net-(MOS62-DRAIN)") (class "Default")
      (node (ref "MOS62") (pin "3") (pinfunction "DRAIN_3") (pintype "bidirectional"))
      (node (ref "R62") (pin "2") (pinfunction "2_2") (pintype "passive"))
    )
    (net (code "268") (name "Net-(MOS63-DRAIN)") (class "Default")
      (node (ref "MOS63") (pin "3") (pinfunction "DRAIN_3") (pintype "bidirectional"))
      (node (ref "R63") (pin "2") (pinfunction "2_2") (pintype "passive"))
    )
    (net (code "269") (name "Net-(MOS64-DRAIN)") (class "Default")
      (node (ref "MOS64") (pin "3") (pinfunction "DRAIN_3") (pintype "bidirectional"))
      (node (ref "R64") (pin "2") (pinfunction "2_2") (pintype "passive"))
    )
    (net (code "270") (name "Net-(MOS65-DRAIN)") (class "Default")
      (node (ref "MOS65") (pin "3") (pinfunction "DRAIN_3") (pintype "bidirectional"))
      (node (ref "R65") (pin "2") (pinfunction "2_2") (pintype "passive"))
    )
    (net (code "271") (name "Net-(MOS66-DRAIN)") (class "Default")
      (node (ref "MOS66") (pin "3") (pinfunction "DRAIN_3") (pintype "bidirectional"))
      (node (ref "R66") (pin "2") (pinfunction "2_2") (pintype "passive"))
    )
    (net (code "272") (name "Net-(MOS67-DRAIN)") (class "Default")
      (node (ref "MOS67") (pin "3") (pinfunction "DRAIN_3") (pintype "bidirectional"))
      (node (ref "R67") (pin "2") (pinfunction "2_2") (pintype "passive"))
    )
    (net (code "273") (name "Net-(MOS68-DRAIN)") (class "Default")
      (node (ref "MOS68") (pin "3") (pinfunction "DRAIN_3") (pintype "bidirectional"))
      (node (ref "R68") (pin "2") (pinfunction "2_2") (pintype "passive"))
    )
    (net (code "274") (name "Net-(MOS69-DRAIN)") (class "Default")
      (node (ref "MOS69") (pin "3") (pinfunction "DRAIN_3") (pintype "bidirectional"))
      (node (ref "R69") (pin "2") (pinfunction "2_2") (pintype "passive"))
    )
    (net (code "275") (name "Net-(MOS70-DRAIN)") (class "Default")
      (node (ref "MOS70") (pin "3") (pinfunction "DRAIN_3") (pintype "bidirectional"))
      (node (ref "R70") (pin "2") (pinfunction "2_2") (pintype "passive"))
    )
    (net (code "276") (name "Net-(MOS71-DRAIN)") (class "Default")
      (node (ref "MOS71") (pin "3") (pinfunction "DRAIN_3") (pintype "bidirectional"))
      (node (ref "R71") (pin "2") (pinfunction "2_2") (pintype "passive"))
    )
    (net (code "277") (name "Net-(MOS72-DRAIN)") (class "Default")
      (node (ref "MOS72") (pin "3") (pinfunction "DRAIN_3") (pintype "bidirectional"))
      (node (ref "R72") (pin "2") (pinfunction "2_2") (pintype "passive"))
    )
    (net (code "278") (name "Net-(MOS73-DRAIN)") (class "Default")
      (node (ref "MOS73") (pin "3") (pinfunction "DRAIN_3") (pintype "bidirectional"))
      (node (ref "R73") (pin "2") (pinfunction "2_2") (pintype "passive"))
    )
    (net (code "279") (name "Net-(MOS74-DRAIN)") (class "Default")
      (node (ref "MOS74") (pin "3") (pinfunction "DRAIN_3") (pintype "bidirectional"))
      (node (ref "R74") (pin "2") (pinfunction "2_2") (pintype "passive"))
    )
    (net (code "280") (name "Net-(MOS75-DRAIN)") (class "Default")
      (node (ref "MOS75") (pin "3") (pinfunction "DRAIN_3") (pintype "bidirectional"))
      (node (ref "R75") (pin "2") (pinfunction "2_2") (pintype "passive"))
    )
    (net (code "281") (name "Net-(MOS76-DRAIN)") (class "Default")
      (node (ref "MOS76") (pin "3") (pinfunction "DRAIN_3") (pintype "bidirectional"))
      (node (ref "R76") (pin "2") (pinfunction "2_2") (pintype "passive"))
    )
    (net (code "282") (name "Net-(MOS77-DRAIN)") (class "Default")
      (node (ref "MOS77") (pin "3") (pinfunction "DRAIN_3") (pintype "bidirectional"))
      (node (ref "R77") (pin "2") (pinfunction "2_2") (pintype "passive"))
    )
    (net (code "283") (name "Net-(MOS78-DRAIN)") (class "Default")
      (node (ref "MOS78") (pin "3") (pinfunction "DRAIN_3") (pintype "bidirectional"))
      (node (ref "R78") (pin "2") (pinfunction "2_2") (pintype "passive"))
    )
    (net (code "284") (name "Net-(MOS79-DRAIN)") (class "Default")
      (node (ref "MOS79") (pin "3") (pinfunction "DRAIN_3") (pintype "bidirectional"))
      (node (ref "R79") (pin "2") (pinfunction "2_2") (pintype "passive"))
    )
    (net (code "285") (name "Net-(MOS80-DRAIN)") (class "Default")
      (node (ref "MOS80") (pin "3") (pinfunction "DRAIN_3") (pintype "bidirectional"))
      (node (ref "R80") (pin "2") (pinfunction "2_2") (pintype "passive"))
    )
    (net (code "286") (name "Net-(MOS81-DRAIN)") (class "Default")
      (node (ref "MOS81") (pin "3") (pinfunction "DRAIN_3") (pintype "bidirectional"))
      (node (ref "R81") (pin "2") (pinfunction "2_2") (pintype "passive"))
    )
    (net (code "287") (name "Net-(MOS82-DRAIN)") (class "Default")
      (node (ref "MOS82") (pin "3") (pinfunction "DRAIN_3") (pintype "bidirectional"))
      (node (ref "R82") (pin "2") (pinfunction "2_2") (pintype "passive"))
    )
    (net (code "288") (name "Net-(MOS83-DRAIN)") (class "Default")
      (node (ref "MOS83") (pin "3") (pinfunction "DRAIN_3") (pintype "bidirectional"))
      (node (ref "R83") (pin "2") (pinfunction "2_2") (pintype "passive"))
    )
    (net (code "289") (name "Net-(MOS84-DRAIN)") (class "Default")
      (node (ref "MOS84") (pin "3") (pinfunction "DRAIN_3") (pintype "bidirectional"))
      (node (ref "R84") (pin "2") (pinfunction "2_2") (pintype "passive"))
    )
    (net (code "290") (name "Net-(MOS85-DRAIN)") (class "Default")
      (node (ref "MOS85") (pin "3") (pinfunction "DRAIN_3") (pintype "bidirectional"))
      (node (ref "R85") (pin "2") (pinfunction "2_2") (pintype "passive"))
    )
    (net (code "291") (name "Net-(MOS86-DRAIN)") (class "Default")
      (node (ref "MOS86") (pin "3") (pinfunction "DRAIN_3") (pintype "bidirectional"))
      (node (ref "R86") (pin "2") (pinfunction "2_2") (pintype "passive"))
    )
    (net (code "292") (name "Net-(MOS87-DRAIN)") (class "Default")
      (node (ref "MOS87") (pin "3") (pinfunction "DRAIN_3") (pintype "bidirectional"))
      (node (ref "R87") (pin "2") (pinfunction "2_2") (pintype "passive"))
    )
    (net (code "293") (name "Net-(MOS88-DRAIN)") (class "Default")
      (node (ref "MOS88") (pin "3") (pinfunction "DRAIN_3") (pintype "bidirectional"))
      (node (ref "R88") (pin "2") (pinfunction "2_2") (pintype "passive"))
    )
    (net (code "294") (name "Net-(MOS89-DRAIN)") (class "Default")
      (node (ref "MOS89") (pin "3") (pinfunction "DRAIN_3") (pintype "bidirectional"))
      (node (ref "R89") (pin "2") (pinfunction "2_2") (pintype "passive"))
    )
    (net (code "295") (name "Net-(MOS90-DRAIN)") (class "Default")
      (node (ref "MOS90") (pin "3") (pinfunction "DRAIN_3") (pintype "bidirectional"))
      (node (ref "R90") (pin "2") (pinfunction "2_2") (pintype "passive"))
    )
    (net (code "296") (name "Net-(MOS91-DRAIN)") (class "Default")
      (node (ref "MOS91") (pin "3") (pinfunction "DRAIN_3") (pintype "bidirectional"))
      (node (ref "R91") (pin "2") (pinfunction "2_2") (pintype "passive"))
    )
    (net (code "297") (name "Net-(MOS92-DRAIN)") (class "Default")
      (node (ref "MOS92") (pin "3") (pinfunction "DRAIN_3") (pintype "bidirectional"))
      (node (ref "R92") (pin "2") (pinfunction "2_2") (pintype "passive"))
    )
    (net (code "298") (name "Net-(MOS93-DRAIN)") (class "Default")
      (node (ref "MOS93") (pin "3") (pinfunction "DRAIN_3") (pintype "bidirectional"))
      (node (ref "R93") (pin "2") (pinfunction "2_2") (pintype "passive"))
    )
    (net (code "299") (name "Net-(MOS94-DRAIN)") (class "Default")
      (node (ref "MOS94") (pin "3") (pinfunction "DRAIN_3") (pintype "bidirectional"))
      (node (ref "R94") (pin "2") (pinfunction "2_2") (pintype "passive"))
    )
    (net (code "300") (name "Net-(MOS95-DRAIN)") (class "Default")
      (node (ref "MOS95") (pin "3") (pinfunction "DRAIN_3") (pintype "bidirectional"))
      (node (ref "R95") (pin "2") (pinfunction "2_2") (pintype "passive"))
    )
    (net (code "301") (name "Net-(MOS96-DRAIN)") (class "Default")
      (node (ref "MOS96") (pin "3") (pinfunction "DRAIN_3") (pintype "bidirectional"))
      (node (ref "R96") (pin "2") (pinfunction "2_2") (pintype "passive"))
    )
    (net (code "302") (name "Net-(MOS97-DRAIN)") (class "Default")
      (node (ref "MOS97") (pin "3") (pinfunction "DRAIN_3") (pintype "bidirectional"))
      (node (ref "R97") (pin "2") (pinfunction "2_2") (pintype "passive"))
    )
    (net (code "303") (name "Net-(MOS98-DRAIN)") (class "Default")
      (node (ref "MOS98") (pin "3") (pinfunction "DRAIN_3") (pintype "bidirectional"))
      (node (ref "R98") (pin "2") (pinfunction "2_2") (pintype "passive"))
    )
    (net (code "304") (name "Net-(MOS99-DRAIN)") (class "Default")
      (node (ref "MOS99") (pin "3") (pinfunction "DRAIN_3") (pintype "bidirectional"))
      (node (ref "R99") (pin "2") (pinfunction "2_2") (pintype "passive"))
    )
    (net (code "305") (name "Net-(MOS100-DRAIN)") (class "Default")
      (node (ref "MOS100") (pin "3") (pinfunction "DRAIN_3") (pintype "bidirectional"))
      (node (ref "R100") (pin "2") (pinfunction "2_2") (pintype "passive"))
    )
  )
)
